# module_vs1003.net
KiCad netlist of a schematic drawn in EAGLE
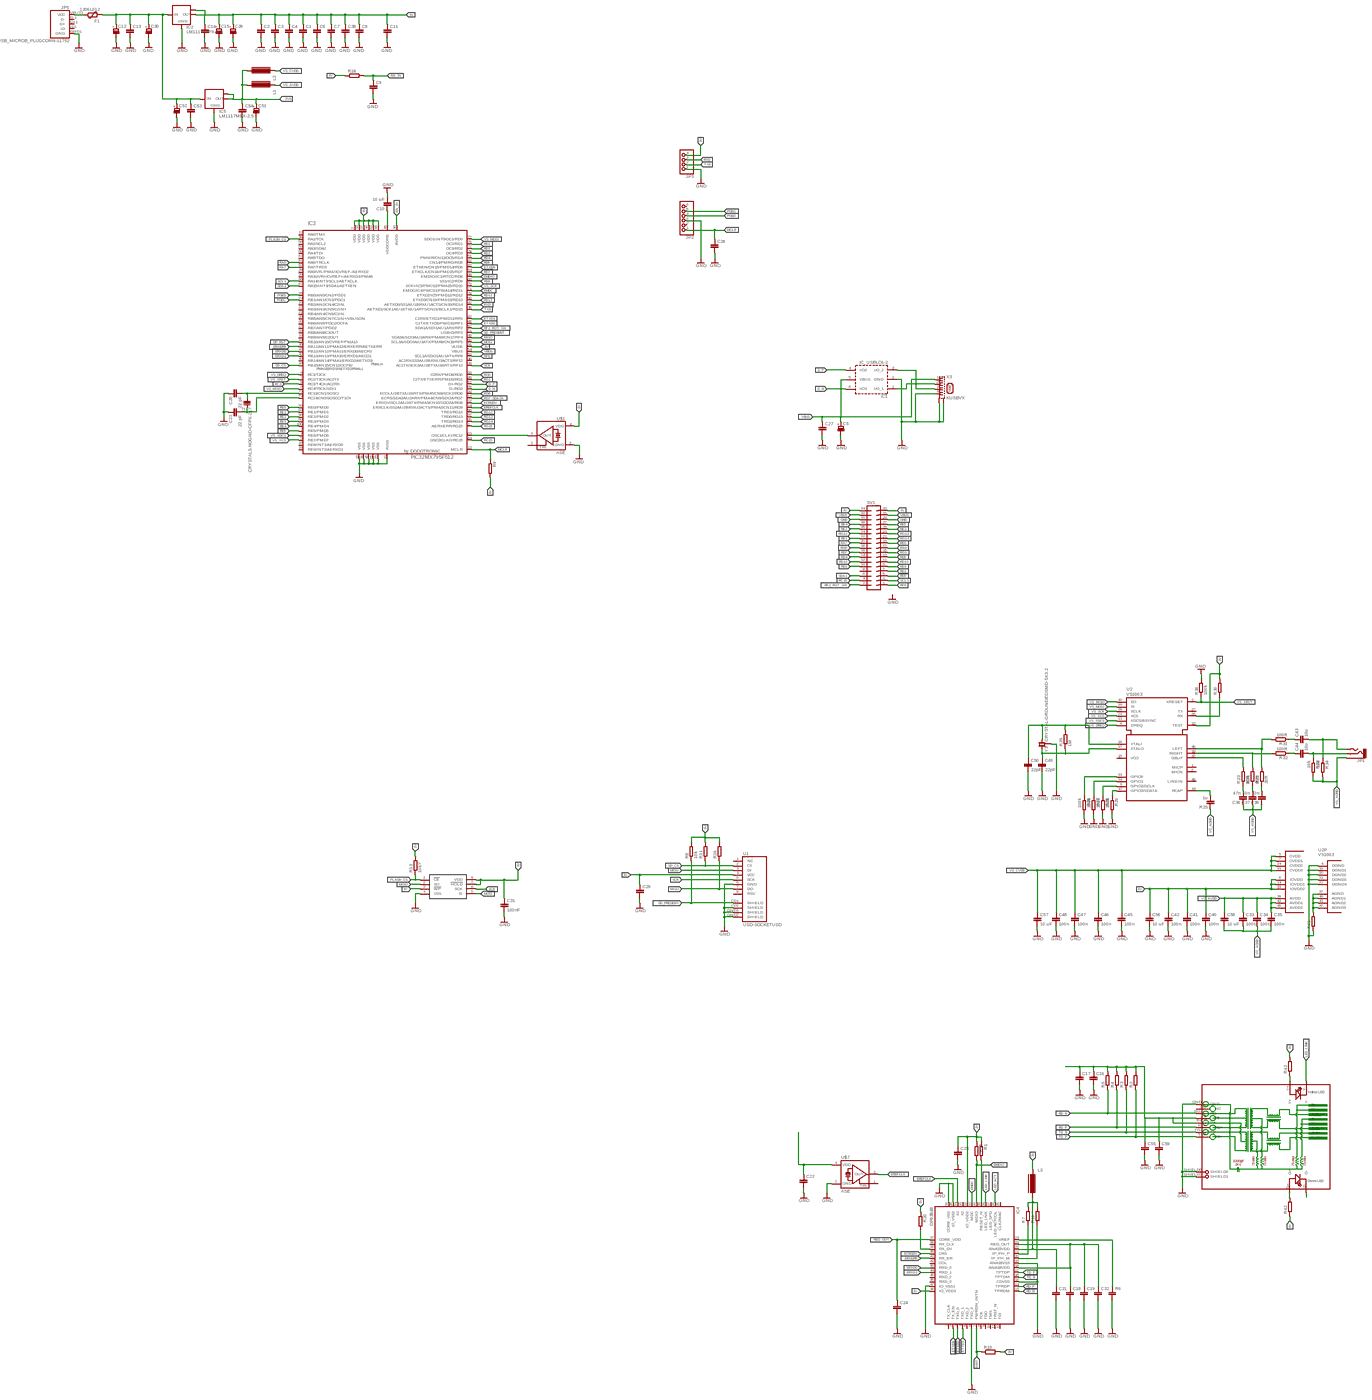
[diagram p0: schematic, sheet 1, overview]
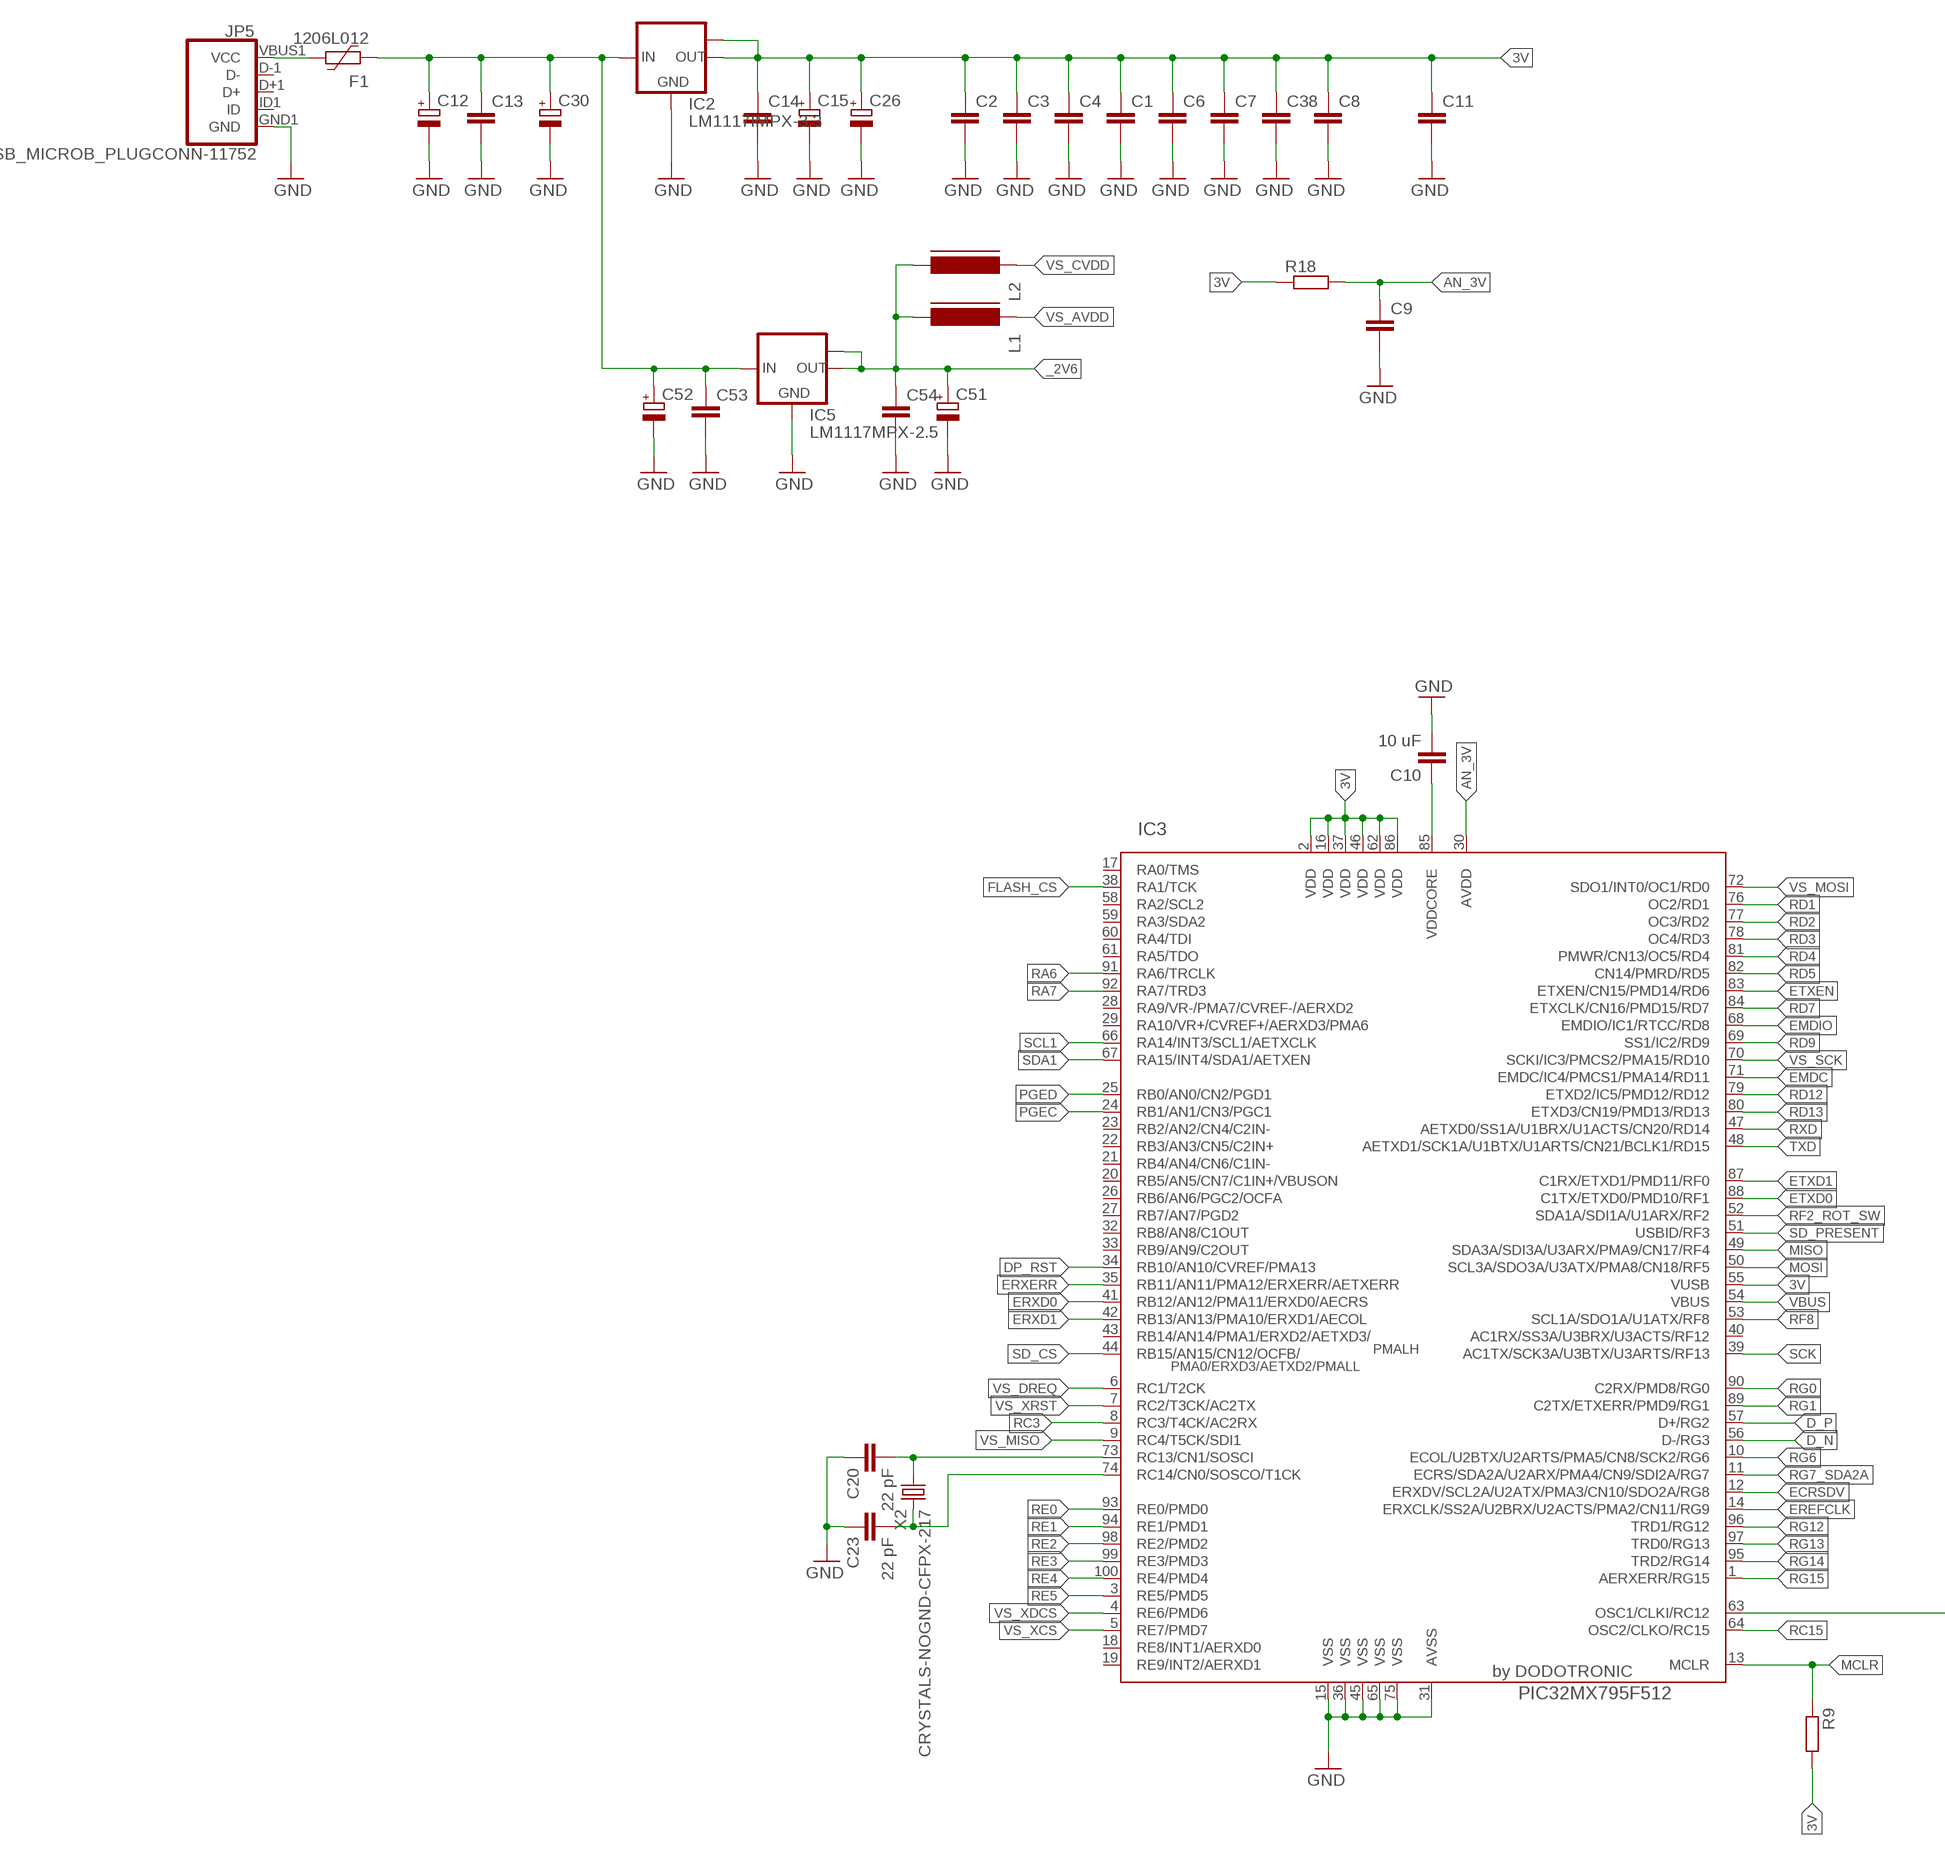
[diagram p1: schematic, sheet 1, part 1 of 4]
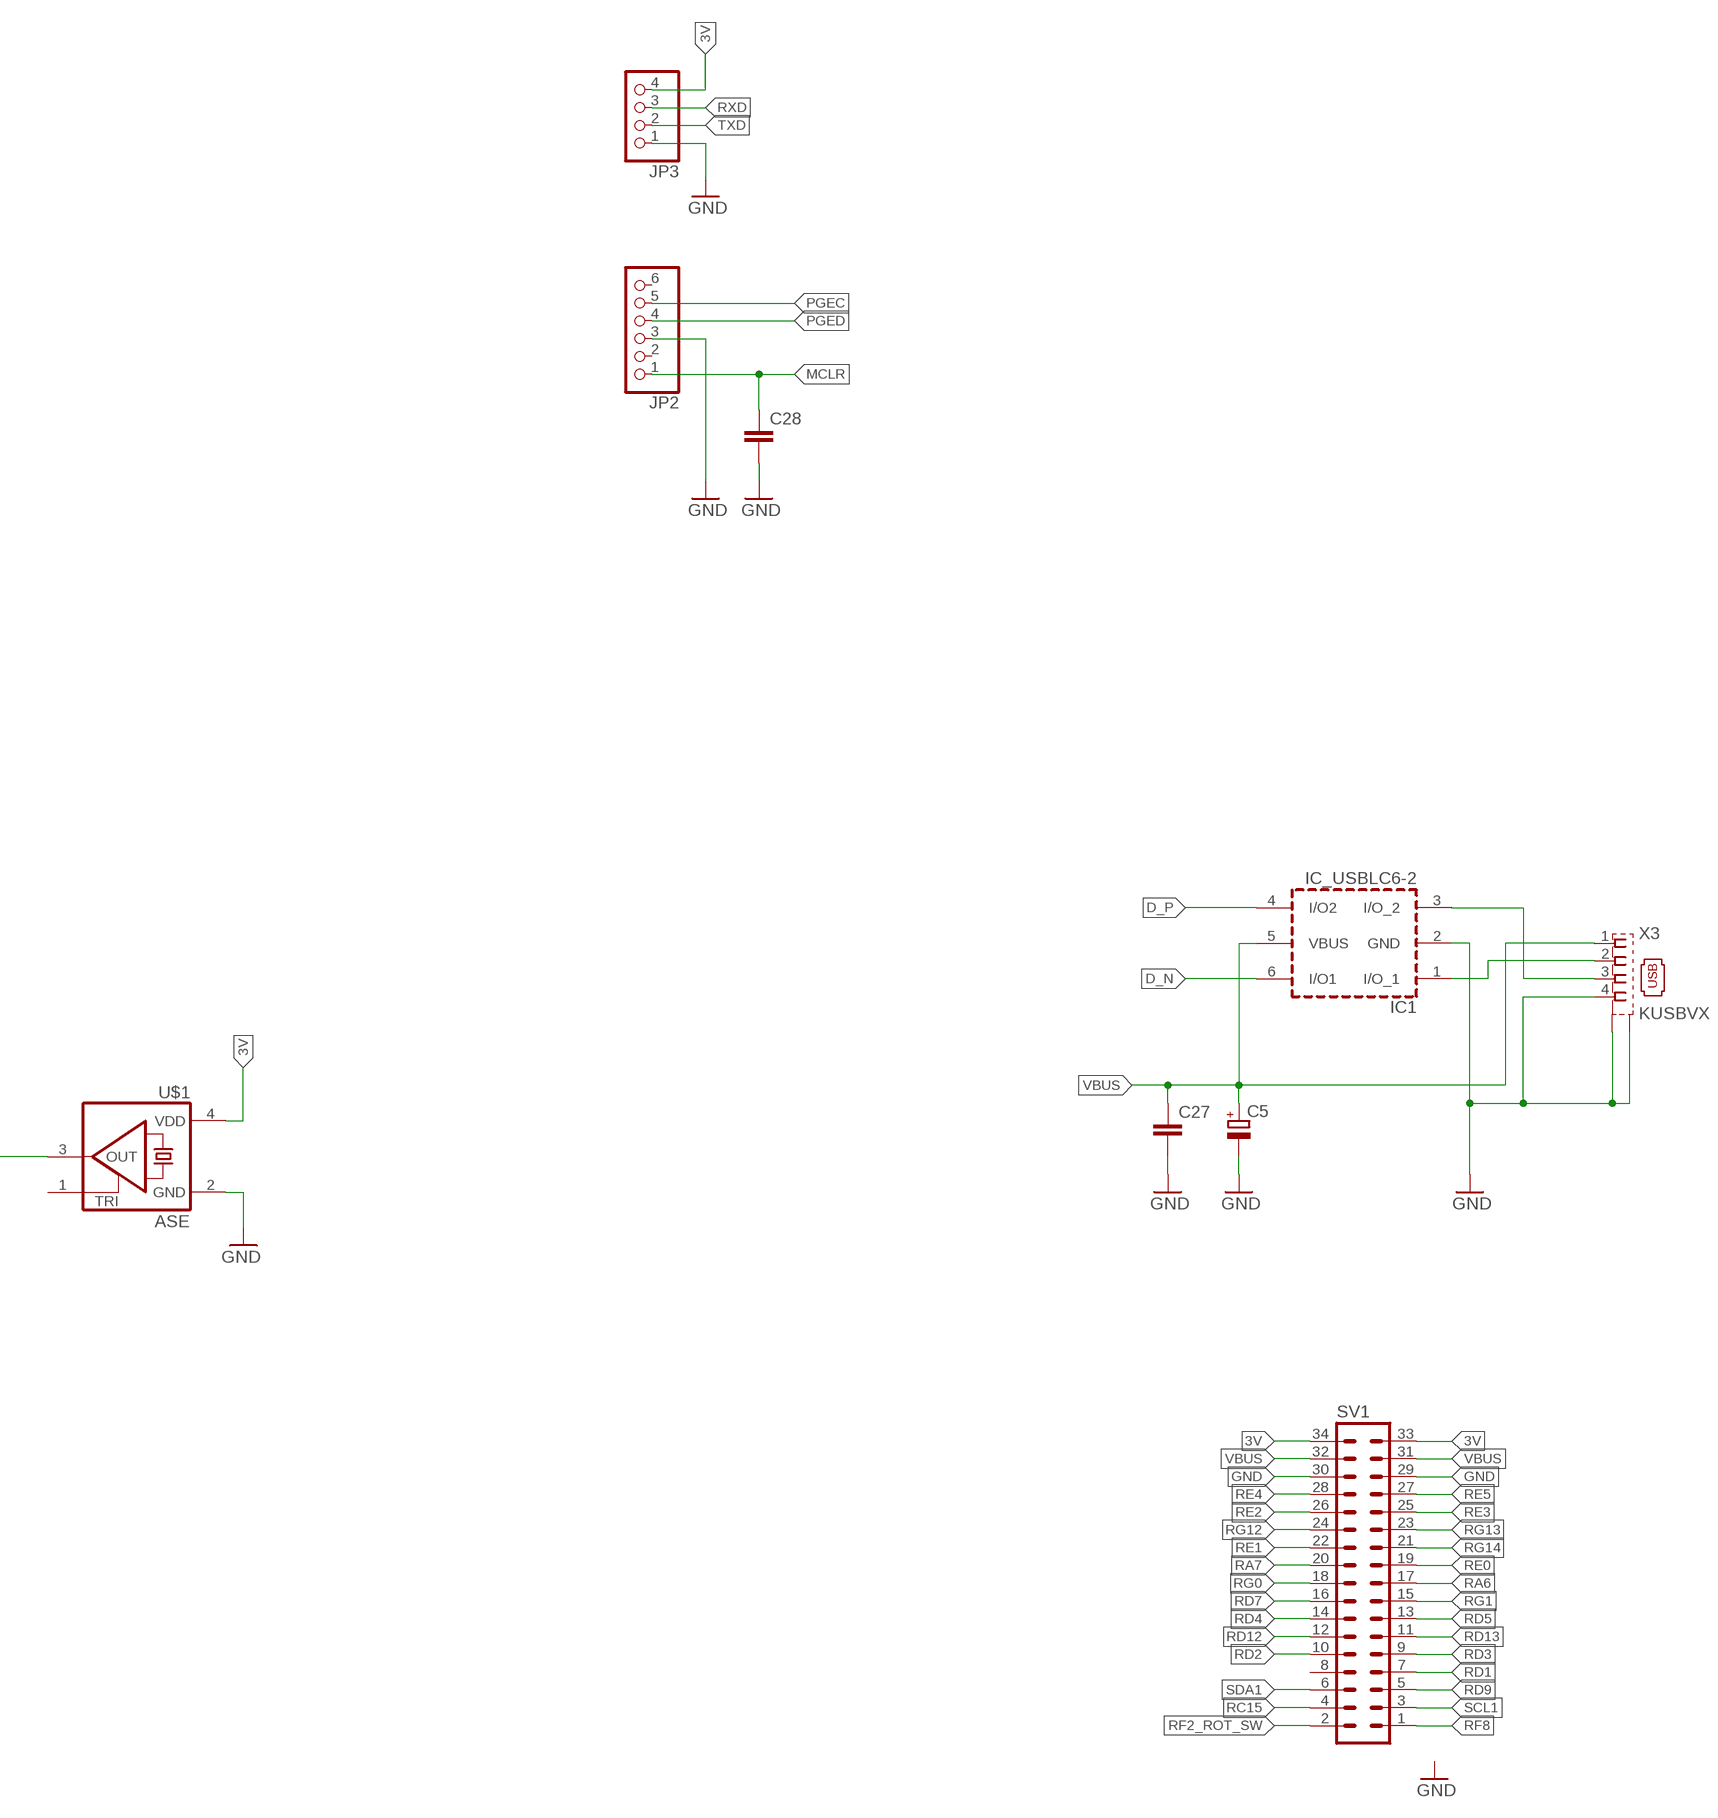
[diagram p2: schematic, sheet 1, part 2 of 4]
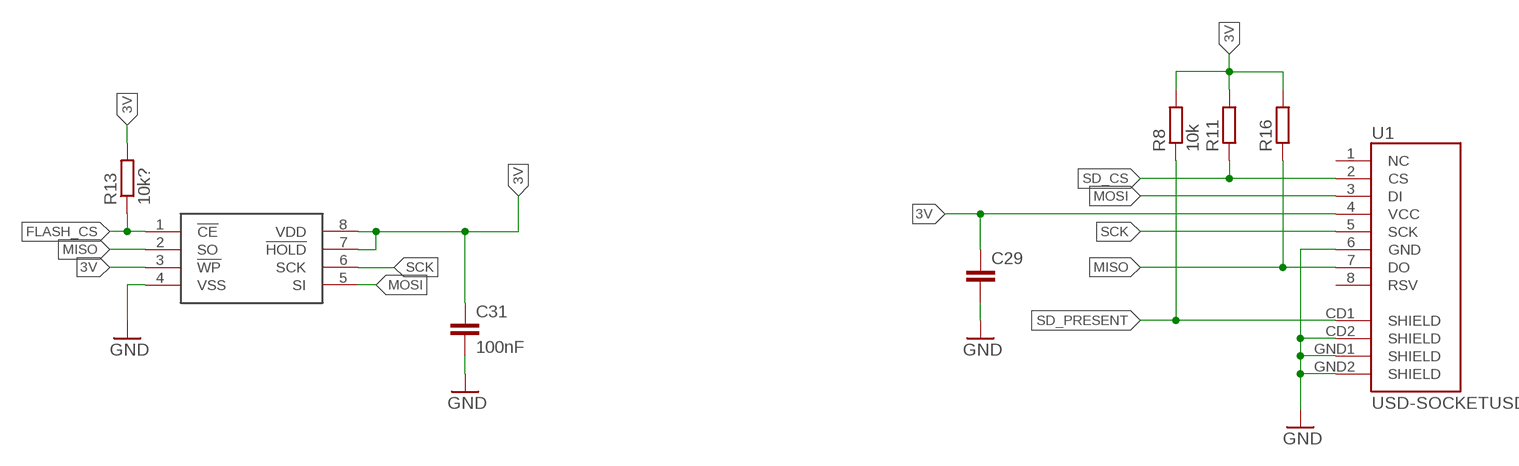
[diagram p3: schematic, sheet 1, part 3 of 4]
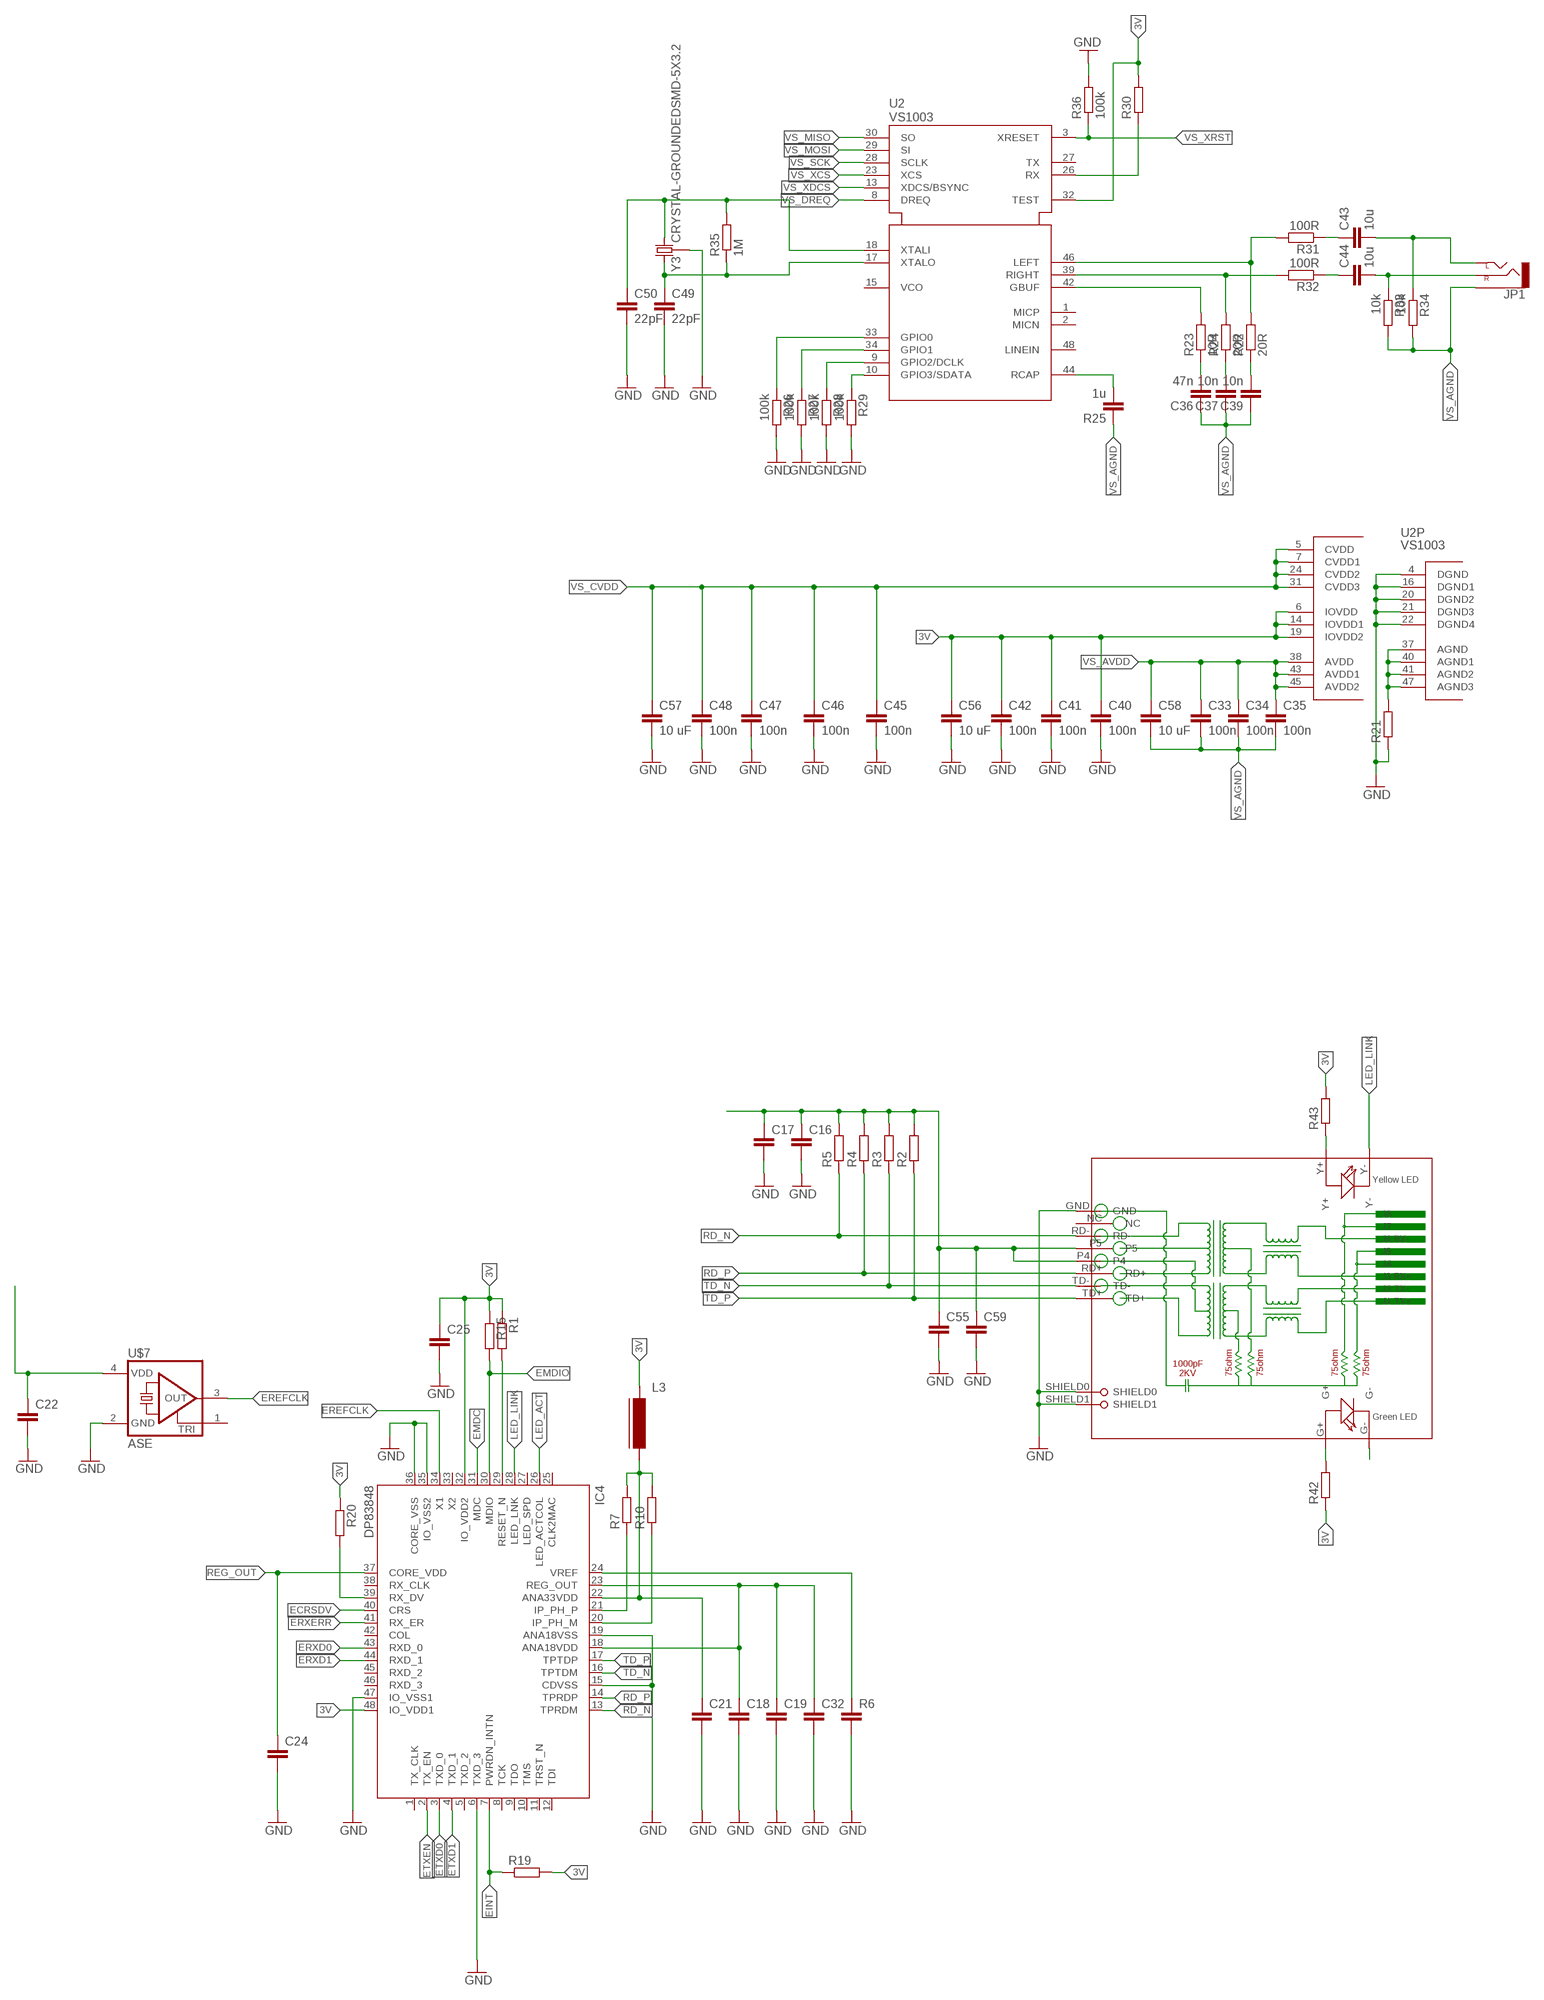
[diagram p4: schematic, sheet 1, part 4 of 4]

(export (version "E")
  (design (tool "Eeschema 10.0.6"))
  (components
    (comp (ref "C1")
      (value "C-EUC0402")
      (footprint "eagle-import:C0402")
      (libsource (lib "eagle-import") (part "C-EUC0402"))
    )
    (comp (ref "C2")
      (value "C-EUC0402")
      (footprint "eagle-import:C0402")
      (libsource (lib "eagle-import") (part "C-EUC0402"))
    )
    (comp (ref "C3")
      (value "C-EUC0402")
      (footprint "eagle-import:C0402")
      (libsource (lib "eagle-import") (part "C-EUC0402"))
    )
    (comp (ref "C4")
      (value "C-EUC0402")
      (footprint "eagle-import:C0402")
      (libsource (lib "eagle-import") (part "C-EUC0402"))
    )
    (comp (ref "C5")
      (value "CPOL-EUSMCA")
      (footprint "eagle-import:SMC_A")
      (libsource (lib "eagle-import") (part "CPOL-EUSMCA"))
    )
    (comp (ref "C6")
      (value "C-EUC0402")
      (footprint "eagle-import:C0402")
      (libsource (lib "eagle-import") (part "C-EUC0402"))
    )
    (comp (ref "C7")
      (value "C-EUC0402")
      (footprint "eagle-import:C0402")
      (libsource (lib "eagle-import") (part "C-EUC0402"))
    )
    (comp (ref "C8")
      (value "C-EUC0402")
      (footprint "eagle-import:C0402")
      (libsource (lib "eagle-import") (part "C-EUC0402"))
    )
    (comp (ref "C9")
      (value "C-EUC0402")
      (footprint "eagle-import:C0402")
      (libsource (lib "eagle-import") (part "C-EUC0402"))
    )
    (comp (ref "C10")
      (value "10 uF")
      (footprint "eagle-import:C0603")
      (libsource (lib "eagle-import") (part "C-EUC0603"))
    )
    (comp (ref "C11")
      (value "C-EUC0402")
      (footprint "eagle-import:C0402")
      (libsource (lib "eagle-import") (part "C-EUC0402"))
    )
    (comp (ref "C12")
      (value "CPOL-EUSMCB")
      (footprint "eagle-import:SMC_B")
      (libsource (lib "eagle-import") (part "CPOL-EUSMCB"))
    )
    (comp (ref "C13")
      (value "C-EUC0603")
      (footprint "eagle-import:C0603")
      (libsource (lib "eagle-import") (part "C-EUC0603"))
    )
    (comp (ref "C14")
      (value "C-EUC0603")
      (footprint "eagle-import:C0603")
      (libsource (lib "eagle-import") (part "C-EUC0603"))
    )
    (comp (ref "C15")
      (value "CPOL-EUSMCB")
      (footprint "eagle-import:SMC_B")
      (libsource (lib "eagle-import") (part "CPOL-EUSMCB"))
    )
    (comp (ref "C16")
      (value "C-EUC0603")
      (footprint "eagle-import:C0603")
      (libsource (lib "eagle-import") (part "C-EUC0603"))
    )
    (comp (ref "C17")
      (value "C-EUC0603")
      (footprint "eagle-import:C0603")
      (libsource (lib "eagle-import") (part "C-EUC0603"))
    )
    (comp (ref "C18")
      (value "C-EUC0402")
      (footprint "eagle-import:C0402")
      (libsource (lib "eagle-import") (part "C-EUC0402"))
    )
    (comp (ref "C19")
      (value "C-EUC0402")
      (footprint "eagle-import:C0402")
      (libsource (lib "eagle-import") (part "C-EUC0402"))
    )
    (comp (ref "C20")
      (value "22 pF")
      (footprint "eagle-import:C0603")
      (libsource (lib "eagle-import") (part "C-EUC0603"))
    )
    (comp (ref "C21")
      (value "C-EUC0402")
      (footprint "eagle-import:C0402")
      (libsource (lib "eagle-import") (part "C-EUC0402"))
    )
    (comp (ref "C22")
      (value "C-EUC0402")
      (footprint "eagle-import:C0402")
      (libsource (lib "eagle-import") (part "C-EUC0402"))
    )
    (comp (ref "C23")
      (value "22 pF")
      (footprint "eagle-import:C0603")
      (libsource (lib "eagle-import") (part "C-EUC0603"))
    )
    (comp (ref "C24")
      (value "C-EUC0603")
      (footprint "eagle-import:C0603")
      (libsource (lib "eagle-import") (part "C-EUC0603"))
    )
    (comp (ref "C25")
      (value "C-EUC0603")
      (footprint "eagle-import:C0603")
      (libsource (lib "eagle-import") (part "C-EUC0603"))
    )
    (comp (ref "C26")
      (value "CPOL-EUSMCA")
      (footprint "eagle-import:SMC_A")
      (libsource (lib "eagle-import") (part "CPOL-EUSMCA"))
    )
    (comp (ref "C27")
      (value "C-EUC0603")
      (footprint "eagle-import:C0603")
      (libsource (lib "eagle-import") (part "C-EUC0603"))
    )
    (comp (ref "C28")
      (value "C-EUC0603")
      (footprint "eagle-import:C0603")
      (libsource (lib "eagle-import") (part "C-EUC0603"))
    )
    (comp (ref "C29")
      (value "C-EUC0603")
      (footprint "eagle-import:C0603")
      (libsource (lib "eagle-import") (part "C-EUC0603"))
    )
    (comp (ref "C30")
      (value "CPOL-EUSMCA")
      (footprint "eagle-import:SMC_A")
      (libsource (lib "eagle-import") (part "CPOL-EUSMCA"))
    )
    (comp (ref "C31")
      (value "100nF")
      (footprint "eagle-import:C0603")
      (libsource (lib "eagle-import") (part "C-EUC0603"))
    )
    (comp (ref "C32")
      (value "C-EUC0603")
      (footprint "eagle-import:C0603")
      (libsource (lib "eagle-import") (part "C-EUC0603"))
    )
    (comp (ref "C33")
      (value "100n")
      (footprint "eagle-import:C0603")
      (libsource (lib "eagle-import") (part "C-EUC0603"))
    )
    (comp (ref "C34")
      (value "100n")
      (footprint "eagle-import:C0603")
      (libsource (lib "eagle-import") (part "C-EUC0603"))
    )
    (comp (ref "C35")
      (value "100n")
      (footprint "eagle-import:C0603")
      (libsource (lib "eagle-import") (part "C-EUC0603"))
    )
    (comp (ref "C36")
      (value "47n")
      (footprint "eagle-import:C0603")
      (libsource (lib "eagle-import") (part "C-EUC0603"))
    )
    (comp (ref "C37")
      (value "10n")
      (footprint "eagle-import:C0603")
      (libsource (lib "eagle-import") (part "C-EUC0603"))
    )
    (comp (ref "C38")
      (value "C-EUC0402")
      (footprint "eagle-import:C0402")
      (libsource (lib "eagle-import") (part "C-EUC0402"))
    )
    (comp (ref "C39")
      (value "10n")
      (footprint "eagle-import:C0603")
      (libsource (lib "eagle-import") (part "C-EUC0603"))
    )
    (comp (ref "C40")
      (value "100n")
      (footprint "eagle-import:C0402")
      (libsource (lib "eagle-import") (part "C-EUC0402"))
    )
    (comp (ref "C41")
      (value "100n")
      (footprint "eagle-import:C0402")
      (libsource (lib "eagle-import") (part "C-EUC0402"))
    )
    (comp (ref "C42")
      (value "100n")
      (footprint "eagle-import:C0402")
      (libsource (lib "eagle-import") (part "C-EUC0402"))
    )
    (comp (ref "C43")
      (value "10u")
      (footprint "eagle-import:C0603")
      (libsource (lib "eagle-import") (part "C-EUC0603"))
    )
    (comp (ref "C44")
      (value "10u")
      (footprint "eagle-import:C0603")
      (libsource (lib "eagle-import") (part "C-EUC0603"))
    )
    (comp (ref "C45")
      (value "100n")
      (footprint "eagle-import:C0402")
      (libsource (lib "eagle-import") (part "C-EUC0402"))
    )
    (comp (ref "C46")
      (value "100n")
      (footprint "eagle-import:C0603")
      (libsource (lib "eagle-import") (part "C-EUC0603"))
    )
    (comp (ref "C47")
      (value "100n")
      (footprint "eagle-import:C0603")
      (libsource (lib "eagle-import") (part "C-EUC0603"))
    )
    (comp (ref "C48")
      (value "100n")
      (footprint "eagle-import:C0603")
      (libsource (lib "eagle-import") (part "C-EUC0603"))
    )
    (comp (ref "C49")
      (value "22pF")
      (footprint "eagle-import:C0603")
      (libsource (lib "eagle-import") (part "C-EUC0603"))
    )
    (comp (ref "C50")
      (value "22pF")
      (footprint "eagle-import:C0603")
      (libsource (lib "eagle-import") (part "C-EUC0603"))
    )
    (comp (ref "C51")
      (value "CPOL-EUSMCB")
      (footprint "eagle-import:SMC_B")
      (libsource (lib "eagle-import") (part "CPOL-EUSMCB"))
    )
    (comp (ref "C52")
      (value "CPOL-EUSMCB")
      (footprint "eagle-import:SMC_B")
      (libsource (lib "eagle-import") (part "CPOL-EUSMCB"))
    )
    (comp (ref "C53")
      (value "C-EUC1206")
      (footprint "eagle-import:C1206")
      (libsource (lib "eagle-import") (part "C-EUC1206"))
    )
    (comp (ref "C54")
      (value "C-EUC1206")
      (footprint "eagle-import:C1206")
      (libsource (lib "eagle-import") (part "C-EUC1206"))
    )
    (comp (ref "C55")
      (value "C-EUC0603")
      (footprint "eagle-import:C0603")
      (libsource (lib "eagle-import") (part "C-EUC0603"))
    )
    (comp (ref "C56")
      (value "10 uF")
      (footprint "eagle-import:C0603")
      (libsource (lib "eagle-import") (part "C-EUC0603"))
    )
    (comp (ref "C57")
      (value "10 uF")
      (footprint "eagle-import:C0603")
      (libsource (lib "eagle-import") (part "C-EUC0603"))
    )
    (comp (ref "C58")
      (value "10 uF")
      (footprint "eagle-import:C0603")
      (libsource (lib "eagle-import") (part "C-EUC0603"))
    )
    (comp (ref "C59")
      (value "C-EUC0603")
      (footprint "eagle-import:C0603")
      (libsource (lib "eagle-import") (part "C-EUC0603"))
    )
    (comp (ref "F1")
      (value "1206L012")
      (footprint "eagle-import:1206L")
      (fields (field (name "MF") "Littelfuse"))
      (libsource (lib "eagle-import") (part "?1206L012"))
    )
    (comp (ref "IC1")
      (value "IC_USBLC6-2")
      (footprint "eagle-import:SOT-23-6L")
      (libsource (lib "eagle-import") (part "IC_USBLC6-2"))
    )
    (comp (ref "IC2")
      (value "LM1117IMPX-3.3")
      (footprint "eagle-import:SOT223")
      (libsource (lib "eagle-import") (part "LM1117IMPX-3.3"))
    )
    (comp (ref "IC3")
      (value "PIC32MX795F512")
      (footprint "eagle-import:TQFP100_12X12")
      (libsource (lib "eagle-import") (part "PIC32MX795F512"))
    )
    (comp (ref "IC4")
      (value "DP83848")
      (footprint "eagle-import:LQFP48")
      (fields (field (name "MPN") "DP83848VYB"))
      (libsource (lib "eagle-import") (part "DP83848"))
    )
    (comp (ref "IC5")
      (value "LM1117MPX-2.5")
      (footprint "eagle-import:SOT223")
      (libsource (lib "eagle-import") (part "LM1117MPX-2.5"))
    )
    (comp (ref "JP1")
      (value "AUDIO-JACKAUDIO_JACK2")
      (footprint "eagle-import:AUDIO-JACK2")
      (libsource (lib "eagle-import") (part "AUDIO-JACKAUDIO_JACK2"))
    )
    (comp (ref "JP2")
      (value "PINHD-1X6")
      (footprint "eagle-import:1X06")
      (libsource (lib "eagle-import") (part "PINHD-1X6"))
    )
    (comp (ref "JP3")
      (value "PINHD-1X4")
      (footprint "eagle-import:1X04")
      (libsource (lib "eagle-import") (part "PINHD-1X4"))
    )
    (comp (ref "JP5")
      (value "USB_MICROB_PLUGCONN-11752")
      (footprint "eagle-import:USB-B-MICRO-SMD_V03")
      (libsource (lib "eagle-import") (part "USB_MICROB_PLUGCONN-11752"))
    )
    (comp (ref "L1")
      (value "FERRITE-0805")
      (footprint "eagle-import:FB805")
      (libsource (lib "eagle-import") (part "FERRITE-0805"))
    )
    (comp (ref "L2")
      (value "FERRITE-0805")
      (footprint "eagle-import:FB805")
      (libsource (lib "eagle-import") (part "FERRITE-0805"))
    )
    (comp (ref "L3")
      (value "FERRITE-0805")
      (footprint "eagle-import:FB805")
      (libsource (lib "eagle-import") (part "FERRITE-0805"))
    )
    (comp (ref "R1")
      (value "R-EU_R0402")
      (footprint "eagle-import:R0402")
      (libsource (lib "eagle-import") (part "R-EU_R0402"))
    )
    (comp (ref "R2")
      (value "R-EU_R0603")
      (footprint "eagle-import:R0603")
      (libsource (lib "eagle-import") (part "R-EU_R0603"))
    )
    (comp (ref "R3")
      (value "R-EU_R0603")
      (footprint "eagle-import:R0603")
      (libsource (lib "eagle-import") (part "R-EU_R0603"))
    )
    (comp (ref "R4")
      (value "R-EU_R0603")
      (footprint "eagle-import:R0603")
      (libsource (lib "eagle-import") (part "R-EU_R0603"))
    )
    (comp (ref "R5")
      (value "R-EU_R0603")
      (footprint "eagle-import:R0603")
      (libsource (lib "eagle-import") (part "R-EU_R0603"))
    )
    (comp (ref "R6")
      (value "C-EUC0603")
      (footprint "eagle-import:C0603")
      (libsource (lib "eagle-import") (part "C-EUC0603"))
    )
    (comp (ref "R7")
      (value "R-EU_R0402")
      (footprint "eagle-import:R0402")
      (libsource (lib "eagle-import") (part "R-EU_R0402"))
    )
    (comp (ref "R8")
      (value "10k")
      (footprint "eagle-import:R0603")
      (libsource (lib "eagle-import") (part "R-EU_R0603"))
    )
    (comp (ref "R9")
      (value "R-EU_R0603")
      (footprint "eagle-import:R0603")
      (libsource (lib "eagle-import") (part "R-EU_R0603"))
    )
    (comp (ref "R10")
      (value "R-EU_R0402")
      (footprint "eagle-import:R0402")
      (libsource (lib "eagle-import") (part "R-EU_R0402"))
    )
    (comp (ref "R11")
      (value "R-EU_R0603")
      (footprint "eagle-import:R0603")
      (libsource (lib "eagle-import") (part "R-EU_R0603"))
    )
    (comp (ref "R13")
      (value "10k?")
      (footprint "eagle-import:R0603")
      (libsource (lib "eagle-import") (part "R-EU_R0603"))
    )
    (comp (ref "R15")
      (value "R-EU_R0603")
      (footprint "eagle-import:R0603")
      (libsource (lib "eagle-import") (part "R-EU_R0603"))
    )
    (comp (ref "R16")
      (value "R-EU_R0603")
      (footprint "eagle-import:R0603")
      (libsource (lib "eagle-import") (part "R-EU_R0603"))
    )
    (comp (ref "R18")
      (value "R-EU_R0805")
      (footprint "eagle-import:R0805")
      (libsource (lib "eagle-import") (part "R-EU_R0805"))
    )
    (comp (ref "R19")
      (value "R-EU_R0402")
      (footprint "eagle-import:R0402")
      (libsource (lib "eagle-import") (part "R-EU_R0402"))
    )
    (comp (ref "R20")
      (value "R-EU_R0603")
      (footprint "eagle-import:R0603")
      (libsource (lib "eagle-import") (part "R-EU_R0603"))
    )
    (comp (ref "R21")
      (value "R-EU_R0603")
      (footprint "eagle-import:R0603")
      (libsource (lib "eagle-import") (part "R-EU_R0603"))
    )
    (comp (ref "R22")
      (value "20R")
      (footprint "eagle-import:R0603")
      (libsource (lib "eagle-import") (part "R-EU_R0603"))
    )
    (comp (ref "R23")
      (value "10R")
      (footprint "eagle-import:R0603")
      (libsource (lib "eagle-import") (part "R-EU_R0603"))
    )
    (comp (ref "R24")
      (value "20R")
      (footprint "eagle-import:R0603")
      (libsource (lib "eagle-import") (part "R-EU_R0603"))
    )
    (comp (ref "R25")
      (value "1u")
      (footprint "eagle-import:C0603")
      (libsource (lib "eagle-import") (part "C-EUC0603"))
    )
    (comp (ref "R26")
      (value "100k")
      (footprint "eagle-import:R0402")
      (libsource (lib "eagle-import") (part "R-EU_R0402"))
    )
    (comp (ref "R27")
      (value "100k")
      (footprint "eagle-import:R0402")
      (libsource (lib "eagle-import") (part "R-EU_R0402"))
    )
    (comp (ref "R28")
      (value "100k")
      (footprint "eagle-import:R0402")
      (libsource (lib "eagle-import") (part "R-EU_R0402"))
    )
    (comp (ref "R29")
      (value "100k")
      (footprint "eagle-import:R0402")
      (libsource (lib "eagle-import") (part "R-EU_R0402"))
    )
    (comp (ref "R30")
      (value "R-EU_0204/7")
      (footprint "eagle-import:0204_7")
      (libsource (lib "eagle-import") (part "R-EU_0204/7"))
    )
    (comp (ref "R31")
      (value "100R")
      (footprint "eagle-import:R0603")
      (libsource (lib "eagle-import") (part "R-EU_R0603"))
    )
    (comp (ref "R32")
      (value "100R")
      (footprint "eagle-import:R0603")
      (libsource (lib "eagle-import") (part "R-EU_R0603"))
    )
    (comp (ref "R33")
      (value "10k")
      (footprint "eagle-import:R0603")
      (libsource (lib "eagle-import") (part "R-EU_R0603"))
    )
    (comp (ref "R34")
      (value "10k")
      (footprint "eagle-import:R0603")
      (libsource (lib "eagle-import") (part "R-EU_R0603"))
    )
    (comp (ref "R35")
      (value "1M")
      (footprint "eagle-import:R0603")
      (libsource (lib "eagle-import") (part "R-EU_R0603"))
    )
    (comp (ref "R36")
      (value "100k")
      (footprint "eagle-import:R0603")
      (libsource (lib "eagle-import") (part "R-EU_R0603"))
    )
    (comp (ref "R42")
      (value "R-EU_R0603")
      (footprint "eagle-import:R0603")
      (libsource (lib "eagle-import") (part "R-EU_R0603"))
    )
    (comp (ref "R43")
      (value "R-EU_R0603")
      (footprint "eagle-import:R0603")
      (libsource (lib "eagle-import") (part "R-EU_R0603"))
    )
    (comp (ref "RJ1")
      (value "HR911105A")
      (footprint "eagle-import:HR911105A")
      (libsource (lib "eagle-import") (part "HR911105A"))
    )
    (comp (ref "SV1")
      (value "ML34L")
      (footprint "eagle-import:ML34L")
      (libsource (lib "eagle-import") (part "ML34L"))
    )
    (comp (ref "U$1")
      (value "ASE")
      (footprint "eagle-import:ASE")
      (libsource (lib "eagle-import") (part "ASE"))
    )
    (comp (ref "U$2")
      (value "SST25VF016BSO8M")
      (footprint "eagle-import:SO-08M")
      (libsource (lib "eagle-import") (part "SST25VF016BSO8M"))
    )
    (comp (ref "U$7")
      (value "ASE")
      (footprint "eagle-import:ASE")
      (libsource (lib "eagle-import") (part "ASE"))
    )
    (comp (ref "U1")
      (value "USD-SOCKETUSD")
      (footprint "eagle-import:USD-SOCKET-PP")
      (libsource (lib "eagle-import") (part "USD-SOCKETUSD"))
    )
    (comp (ref "U2")
      (value "VS1003")
      (footprint "eagle-import:LQFP48")
      (libsource (lib "eagle-import") (part "VS1003"))
    )
    (comp (ref "X2")
      (value "CRYSTALS-NOGND-CFPX-217")
      (footprint "eagle-import:3.2X1.5-2-PAD")
      (libsource (lib "eagle-import") (part "CRYSTALS-NOGND-CFPX-217"))
    )
    (comp (ref "X3")
      (value "KUSBVX")
      (footprint "eagle-import:KUSBVX")
      (libsource (lib "eagle-import") (part "KUSBVX"))
    )
    (comp (ref "Y3")
      (value "CRYSTAL-GROUNDEDSMD-5X3.2")
      (footprint "eagle-import:CRYSTAL-SMD-5X3.2-4PAD")
      (libsource (lib "eagle-import") (part "CRYSTAL-GROUNDEDSMD-5X3.2"))
    )
  )
  (nets
    (net (code "1") (name "/A3V") (class "Default")
      (node (ref "C16") (pin "1") (pinfunction "1_1") (pintype "passive"))
      (node (ref "C17") (pin "1") (pinfunction "1_1") (pintype "passive"))
      (node (ref "C21") (pin "1") (pinfunction "1_1") (pintype "passive"))
      (node (ref "C55") (pin "1") (pinfunction "1_1") (pintype "passive"))
      (node (ref "C59") (pin "1") (pinfunction "1_1") (pintype "passive"))
      (node (ref "IC4") (pin "22") (pinfunction "ANA33VDD_22") (pintype "power_in"))
      (node (ref "L3") (pin "2") (pinfunction "2_2") (pintype "passive"))
      (node (ref "R10") (pin "2") (pinfunction "2_2") (pintype "passive"))
      (node (ref "R2") (pin "2") (pinfunction "2_2") (pintype "passive"))
      (node (ref "R3") (pin "2") (pinfunction "2_2") (pintype "passive"))
      (node (ref "R4") (pin "2") (pinfunction "2_2") (pintype "passive"))
      (node (ref "R5") (pin "2") (pinfunction "2_2") (pintype "passive"))
      (node (ref "R7") (pin "2") (pinfunction "2_2") (pintype "passive"))
      (node (ref "RJ1") (pin "P4") (pinfunction "P4_P4") (pintype "bidirectional"))
      (node (ref "RJ1") (pin "P5") (pinfunction "P5_P5") (pintype "bidirectional"))
    )
    (net (code "2") (name "3V") (class "Default")
      (node (ref "C1") (pin "1") (pinfunction "1_1") (pintype "passive"))
      (node (ref "C11") (pin "1") (pinfunction "1_1") (pintype "passive"))
      (node (ref "C14") (pin "1") (pinfunction "1_1") (pintype "passive"))
      (node (ref "C15") (pin "+") (pinfunction "+_+") (pintype "passive"))
      (node (ref "C2") (pin "1") (pinfunction "1_1") (pintype "passive"))
      (node (ref "C22") (pin "1") (pinfunction "1_1") (pintype "passive"))
      (node (ref "C25") (pin "1") (pinfunction "1_1") (pintype "passive"))
      (node (ref "C26") (pin "+") (pinfunction "+_+") (pintype "passive"))
      (node (ref "C29") (pin "1") (pinfunction "1_1") (pintype "passive"))
      (node (ref "C3") (pin "1") (pinfunction "1_1") (pintype "passive"))
      (node (ref "C31") (pin "1") (pinfunction "1_1") (pintype "passive"))
      (node (ref "C38") (pin "1") (pinfunction "1_1") (pintype "passive"))
      (node (ref "C4") (pin "1") (pinfunction "1_1") (pintype "passive"))
      (node (ref "C40") (pin "1") (pinfunction "1_1") (pintype "passive"))
      (node (ref "C41") (pin "1") (pinfunction "1_1") (pintype "passive"))
      (node (ref "C42") (pin "1") (pinfunction "1_1") (pintype "passive"))
      (node (ref "C56") (pin "1") (pinfunction "1_1") (pintype "passive"))
      (node (ref "C6") (pin "1") (pinfunction "1_1") (pintype "passive"))
      (node (ref "C7") (pin "1") (pinfunction "1_1") (pintype "passive"))
      (node (ref "C8") (pin "1") (pinfunction "1_1") (pintype "passive"))
      (node (ref "IC2") (pin "2") (pinfunction "OUT_2") (pintype "passive"))
      (node (ref "IC2") (pin "TAB") (pinfunction "OUT1_TAB") (pintype "passive"))
      (node (ref "IC3") (pin "16") (pinfunction "VDD_16") (pintype "power_in"))
      (node (ref "IC3") (pin "2") (pinfunction "VDD_2") (pintype "power_in"))
      (node (ref "IC3") (pin "37") (pinfunction "VDD_37") (pintype "power_in"))
      (node (ref "IC3") (pin "46") (pinfunction "VDD_46") (pintype "power_in"))
      (node (ref "IC3") (pin "55") (pinfunction "VUSB_55") (pintype "bidirectional"))
      (node (ref "IC3") (pin "62") (pinfunction "VDD_62") (pintype "power_in"))
      (node (ref "IC3") (pin "86") (pinfunction "VDD_86") (pintype "power_in"))
      (node (ref "IC4") (pin "32") (pinfunction "IO_VDD2_32") (pintype "power_in"))
      (node (ref "IC4") (pin "48") (pinfunction "IO_VDD1_48") (pintype "power_in"))
      (node (ref "JP3") (pin "4") (pinfunction "4_4") (pintype "passive"))
      (node (ref "L3") (pin "1") (pinfunction "1_1") (pintype "passive"))
      (node (ref "R1") (pin "1") (pinfunction "1_1") (pintype "passive"))
      (node (ref "R11") (pin "2") (pinfunction "2_2") (pintype "passive"))
      (node (ref "R13") (pin "2") (pinfunction "2_2") (pintype "passive"))
      (node (ref "R15") (pin "1") (pinfunction "1_1") (pintype "passive"))
      (node (ref "R16") (pin "2") (pinfunction "2_2") (pintype "passive"))
      (node (ref "R18") (pin "1") (pinfunction "1_1") (pintype "passive"))
      (node (ref "R19") (pin "2") (pinfunction "2_2") (pintype "passive"))
      (node (ref "R20") (pin "1") (pinfunction "1_1") (pintype "passive"))
      (node (ref "R30") (pin "2") (pinfunction "2_2") (pintype "passive"))
      (node (ref "R42") (pin "1") (pinfunction "1_1") (pintype "passive"))
      (node (ref "R43") (pin "2") (pinfunction "2_2") (pintype "passive"))
      (node (ref "R8") (pin "2") (pinfunction "2_2") (pintype "passive"))
      (node (ref "R9") (pin "2") (pinfunction "2_2") (pintype "passive"))
      (node (ref "SV1") (pin "33") (pinfunction "33_33") (pintype "passive"))
      (node (ref "SV1") (pin "34") (pinfunction "34_34") (pintype "passive"))
      (node (ref "U$1") (pin "4") (pinfunction "VDD_4") (pintype "power_in"))
      (node (ref "U$2") (pin "3") (pinfunction "~{WP}_3") (pintype "bidirectional"))
      (node (ref "U$2") (pin "7") (pinfunction "~{HOLD}_7") (pintype "bidirectional"))
      (node (ref "U$2") (pin "8") (pinfunction "VDD_8") (pintype "bidirectional"))
      (node (ref "U$7") (pin "4") (pinfunction "VDD_4") (pintype "power_in"))
      (node (ref "U1") (pin "4") (pinfunction "VCC_4") (pintype "bidirectional"))
      (node (ref "U2") (pin "14") (pinfunction "IOVDD1_14") (pintype "power_in"))
      (node (ref "U2") (pin "19") (pinfunction "IOVDD2_19") (pintype "power_in"))
      (node (ref "U2") (pin "32") (pinfunction "TEST_32") (pintype "bidirectional"))
      (node (ref "U2") (pin "6") (pinfunction "IOVDD_6") (pintype "power_in"))
    )
    (net (code "3") (name "AN_3V") (class "Default")
      (node (ref "C9") (pin "1") (pinfunction "1_1") (pintype "passive"))
      (node (ref "IC3") (pin "30") (pinfunction "AVDD_30") (pintype "bidirectional"))
      (node (ref "R18") (pin "2") (pinfunction "2_2") (pintype "passive"))
    )
    (net (code "4") (name "DP_RST") (class "Default")
      (node (ref "IC3") (pin "34") (pinfunction "RB10/AN10/CVREF/PMA13_34") (pintype "bidirectional"))
      (node (ref "IC4") (pin "29") (pinfunction "RESET_N_29") (pintype "input"))
      (node (ref "R1") (pin "2") (pinfunction "2_2") (pintype "passive"))
    )
    (net (code "5") (name "D_N") (class "Default")
      (node (ref "IC1") (pin "6") (pinfunction "I/O1_6") (pintype "bidirectional"))
      (node (ref "IC3") (pin "56") (pinfunction "D-/RG3_56") (pintype "bidirectional"))
    )
    (net (code "6") (name "D_P") (class "Default")
      (node (ref "IC1") (pin "4") (pinfunction "I/O2_4") (pintype "bidirectional"))
      (node (ref "IC3") (pin "57") (pinfunction "D+/RG2_57") (pintype "bidirectional"))
    )
    (net (code "7") (name "ECRSDV") (class "Default")
      (node (ref "IC3") (pin "12") (pinfunction "ERXDV/SCL2A/U2ATX/PMA3/CN10/SDO2A/RG8_12") (pintype "bidirectional"))
      (node (ref "IC4") (pin "40") (pinfunction "CRS_40") (pintype "bidirectional"))
    )
    (net (code "8") (name "EINT") (class "Default")
      (node (ref "IC4") (pin "7") (pinfunction "PWRDN_INTN_7") (pintype "bidirectional"))
      (node (ref "R19") (pin "1") (pinfunction "1_1") (pintype "passive"))
    )
    (net (code "9") (name "EMDC") (class "Default")
      (node (ref "IC3") (pin "71") (pinfunction "EMDC/IC4/PMCS1/PMA14/RD11_71") (pintype "bidirectional"))
      (node (ref "IC4") (pin "31") (pinfunction "MDC_31") (pintype "input"))
    )
    (net (code "10") (name "EMDIO") (class "Default")
      (node (ref "IC3") (pin "68") (pinfunction "EMDIO/IC1/RTCC/RD8_68") (pintype "bidirectional"))
      (node (ref "IC4") (pin "30") (pinfunction "MDIO_30") (pintype "bidirectional"))
      (node (ref "R15") (pin "2") (pinfunction "2_2") (pintype "passive"))
    )
    (net (code "11") (name "EREFCLK") (class "Default")
      (node (ref "IC3") (pin "14") (pinfunction "ERXCLK/SS2A/U2BRX/U2ACTS/PMA2/CN11/RG9_14") (pintype "bidirectional"))
      (node (ref "IC4") (pin "34") (pinfunction "X1_34") (pintype "input"))
      (node (ref "U$7") (pin "3") (pinfunction "OUT_3") (pintype "output"))
    )
    (net (code "12") (name "ERXD0") (class "Default")
      (node (ref "IC3") (pin "41") (pinfunction "RB12/AN12/PMA11/ERXD0/AECRS_41") (pintype "bidirectional"))
      (node (ref "IC4") (pin "43") (pinfunction "RXD_0_43") (pintype "bidirectional"))
    )
    (net (code "13") (name "ERXD1") (class "Default")
      (node (ref "IC3") (pin "42") (pinfunction "RB13/AN13/PMA10/ERXD1/AECOL_42") (pintype "bidirectional"))
      (node (ref "IC4") (pin "44") (pinfunction "RXD_1_44") (pintype "bidirectional"))
    )
    (net (code "14") (name "ERXERR") (class "Default")
      (node (ref "IC3") (pin "35") (pinfunction "RB11/AN11/PMA12/ERXERR/AETXERR_35") (pintype "bidirectional"))
      (node (ref "IC4") (pin "41") (pinfunction "RX_ER_41") (pintype "bidirectional"))
    )
    (net (code "15") (name "ETXD0") (class "Default")
      (node (ref "IC3") (pin "88") (pinfunction "C1TX/ETXD0/PMD10/RF1_88") (pintype "bidirectional"))
      (node (ref "IC4") (pin "3") (pinfunction "TXD_0_3") (pintype "bidirectional"))
    )
    (net (code "16") (name "ETXD1") (class "Default")
      (node (ref "IC3") (pin "87") (pinfunction "C1RX/ETXD1/PMD11/RF0_87") (pintype "bidirectional"))
      (node (ref "IC4") (pin "4") (pinfunction "TXD_1_4") (pintype "bidirectional"))
    )
    (net (code "17") (name "ETXEN") (class "Default")
      (node (ref "IC3") (pin "83") (pinfunction "ETXEN/CN15/PMD14/RD6_83") (pintype "bidirectional"))
      (node (ref "IC4") (pin "2") (pinfunction "TX_EN_2") (pintype "bidirectional"))
    )
    (net (code "18") (name "FLASH_CS") (class "Default")
      (node (ref "IC3") (pin "38") (pinfunction "RA1/TCK_38") (pintype "bidirectional"))
      (node (ref "R13") (pin "1") (pinfunction "1_1") (pintype "passive"))
      (node (ref "U$2") (pin "1") (pinfunction "~{CE}_1") (pintype "bidirectional"))
    )
    (net (code "19") (name "GND") (class "Default")
      (node (ref "C1") (pin "2") (pinfunction "2_2") (pintype "passive"))
      (node (ref "C10") (pin "2") (pinfunction "2_2") (pintype "passive"))
      (node (ref "C11") (pin "2") (pinfunction "2_2") (pintype "passive"))
      (node (ref "C12") (pin "-") (pinfunction "-_-") (pintype "passive"))
      (node (ref "C13") (pin "2") (pinfunction "2_2") (pintype "passive"))
      (node (ref "C14") (pin "2") (pinfunction "2_2") (pintype "passive"))
      (node (ref "C15") (pin "-") (pinfunction "-_-") (pintype "passive"))
      (node (ref "C16") (pin "2") (pinfunction "2_2") (pintype "passive"))
      (node (ref "C17") (pin "2") (pinfunction "2_2") (pintype "passive"))
      (node (ref "C18") (pin "2") (pinfunction "2_2") (pintype "passive"))
      (node (ref "C19") (pin "2") (pinfunction "2_2") (pintype "passive"))
      (node (ref "C2") (pin "2") (pinfunction "2_2") (pintype "passive"))
      (node (ref "C20") (pin "1") (pinfunction "1_1") (pintype "passive"))
      (node (ref "C21") (pin "2") (pinfunction "2_2") (pintype "passive"))
      (node (ref "C22") (pin "2") (pinfunction "2_2") (pintype "passive"))
      (node (ref "C23") (pin "1") (pinfunction "1_1") (pintype "passive"))
      (node (ref "C24") (pin "2") (pinfunction "2_2") (pintype "passive"))
      (node (ref "C25") (pin "2") (pinfunction "2_2") (pintype "passive"))
      (node (ref "C26") (pin "-") (pinfunction "-_-") (pintype "passive"))
      (node (ref "C27") (pin "2") (pinfunction "2_2") (pintype "passive"))
      (node (ref "C28") (pin "2") (pinfunction "2_2") (pintype "passive"))
      (node (ref "C29") (pin "2") (pinfunction "2_2") (pintype "passive"))
      (node (ref "C3") (pin "2") (pinfunction "2_2") (pintype "passive"))
      (node (ref "C30") (pin "-") (pinfunction "-_-") (pintype "passive"))
      (node (ref "C31") (pin "2") (pinfunction "2_2") (pintype "passive"))
      (node (ref "C32") (pin "2") (pinfunction "2_2") (pintype "passive"))
      (node (ref "C38") (pin "2") (pinfunction "2_2") (pintype "passive"))
      (node (ref "C4") (pin "2") (pinfunction "2_2") (pintype "passive"))
      (node (ref "C40") (pin "2") (pinfunction "2_2") (pintype "passive"))
      (node (ref "C41") (pin "2") (pinfunction "2_2") (pintype "passive"))
      (node (ref "C42") (pin "2") (pinfunction "2_2") (pintype "passive"))
      (node (ref "C45") (pin "2") (pinfunction "2_2") (pintype "passive"))
      (node (ref "C46") (pin "2") (pinfunction "2_2") (pintype "passive"))
      (node (ref "C47") (pin "2") (pinfunction "2_2") (pintype "passive"))
      (node (ref "C48") (pin "2") (pinfunction "2_2") (pintype "passive"))
      (node (ref "C49") (pin "2") (pinfunction "2_2") (pintype "passive"))
      (node (ref "C5") (pin "-") (pinfunction "-_-") (pintype "passive"))
      (node (ref "C50") (pin "2") (pinfunction "2_2") (pintype "passive"))
      (node (ref "C51") (pin "-") (pinfunction "-_-") (pintype "passive"))
      (node (ref "C52") (pin "-") (pinfunction "-_-") (pintype "passive"))
      (node (ref "C53") (pin "2") (pinfunction "2_2") (pintype "passive"))
      (node (ref "C54") (pin "2") (pinfunction "2_2") (pintype "passive"))
      (node (ref "C55") (pin "2") (pinfunction "2_2") (pintype "passive"))
      (node (ref "C56") (pin "2") (pinfunction "2_2") (pintype "passive"))
      (node (ref "C57") (pin "2") (pinfunction "2_2") (pintype "passive"))
      (node (ref "C59") (pin "2") (pinfunction "2_2") (pintype "passive"))
      (node (ref "C6") (pin "2") (pinfunction "2_2") (pintype "passive"))
      (node (ref "C7") (pin "2") (pinfunction "2_2") (pintype "passive"))
      (node (ref "C8") (pin "2") (pinfunction "2_2") (pintype "passive"))
      (node (ref "C9") (pin "2") (pinfunction "2_2") (pintype "passive"))
      (node (ref "IC1") (pin "2") (pinfunction "GND_2") (pintype "bidirectional"))
      (node (ref "IC2") (pin "1") (pinfunction "GND_1") (pintype "input"))
      (node (ref "IC3") (pin "15") (pinfunction "VSS_15") (pintype "power_in"))
      (node (ref "IC3") (pin "31") (pinfunction "AVSS_31") (pintype "bidirectional"))
      (node (ref "IC3") (pin "36") (pinfunction "VSS_36") (pintype "power_in"))
      (node (ref "IC3") (pin "45") (pinfunction "VSS_45") (pintype "power_in"))
      (node (ref "IC3") (pin "65") (pinfunction "VSS_65") (pintype "power_in"))
      (node (ref "IC3") (pin "75") (pinfunction "VSS_75") (pintype "power_in"))
      (node (ref "IC4") (pin "15") (pinfunction "CDVSS_15") (pintype "power_in"))
      (node (ref "IC4") (pin "19") (pinfunction "ANA18VSS_19") (pintype "power_in"))
      (node (ref "IC4") (pin "35") (pinfunction "IO_VSS2_35") (pintype "power_in"))
      (node (ref "IC4") (pin "36") (pinfunction "CORE_VSS_36") (pintype "power_in"))
      (node (ref "IC4") (pin "47") (pinfunction "IO_VSS1_47") (pintype "power_in"))
      (node (ref "IC4") (pin "6") (pinfunction "TXD_3_6") (pintype "bidirectional"))
      (node (ref "IC5") (pin "1") (pinfunction "GND_1") (pintype "input"))
      (node (ref "JP2") (pin "3") (pinfunction "3_3") (pintype "passive"))
      (node (ref "JP3") (pin "1") (pinfunction "1_1") (pintype "passive"))
      (node (ref "JP5") (pin "GND1") (pinfunction "GND_GND1") (pintype "bidirectional"))
      (node (ref "R21") (pin "1") (pinfunction "1_1") (pintype "passive"))
      (node (ref "R26") (pin "2") (pinfunction "2_2") (pintype "passive"))
      (node (ref "R27") (pin "2") (pinfunction "2_2") (pintype "passive"))
      (node (ref "R28") (pin "2") (pinfunction "2_2") (pintype "passive"))
      (node (ref "R29") (pin "2") (pinfunction "2_2") (pintype "passive"))
      (node (ref "R36") (pin "2") (pinfunction "2_2") (pintype "passive"))
      (node (ref "R6") (pin "2") (pinfunction "2_2") (pintype "passive"))
      (node (ref "RJ1") (pin "GND") (pinfunction "GND_GND") (pintype "bidirectional"))
      (node (ref "RJ1") (pin "SHIELD0") (pinfunction "SHIELD0_SHIELD0") (pintype "bidirectional"))
      (node (ref "RJ1") (pin "SHIELD1") (pinfunction "SHIELD1_SHIELD1") (pintype "bidirectional"))
      (node (ref "SV1") (pin "29") (pinfunction "29_29") (pintype "passive"))
      (node (ref "SV1") (pin "30") (pinfunction "30_30") (pintype "passive"))
      (node (ref "U$1") (pin "2") (pinfunction "GND_2") (pintype "power_in"))
      (node (ref "U$2") (pin "4") (pinfunction "VSS_4") (pintype "bidirectional"))
      (node (ref "U$7") (pin "2") (pinfunction "GND_2") (pintype "power_in"))
      (node (ref "U1") (pin "6") (pinfunction "GND_6") (pintype "bidirectional"))
      (node (ref "U1") (pin "CD2") (pinfunction "SHIELD_CD2") (pintype "bidirectional"))
      (node (ref "U1") (pin "GND1") (pinfunction "SHIELD_GND1") (pintype "bidirectional"))
      (node (ref "U1") (pin "GND2") (pinfunction "SHIELD_GND2") (pintype "bidirectional"))
      (node (ref "U2") (pin "16") (pinfunction "DGND1_16") (pintype "power_in"))
      (node (ref "U2") (pin "20") (pinfunction "DGND2_20") (pintype "power_in"))
      (node (ref "U2") (pin "21") (pinfunction "DGND3_21") (pintype "power_in"))
      (node (ref "U2") (pin "22") (pinfunction "DGND4_22") (pintype "power_in"))
      (node (ref "U2") (pin "4") (pinfunction "DGND_4") (pintype "power_in"))
      (node (ref "X3") (pin "4") (pinfunction "4_4") (pintype "passive"))
      (node (ref "X3") (pin "M1") (pinfunction "S1_M1") (pintype "passive"))
      (node (ref "X3") (pin "M2") (pinfunction "S2_M2") (pintype "passive"))
      (node (ref "Y3") (pin "2") (pinfunction "3_2") (pintype "passive"))
      (node (ref "Y3") (pin "4") (pinfunction "3_4") (pintype "passive"))
    )
    (net (code "20") (name "LED_ACT") (class "Default")
      (node (ref "IC4") (pin "26") (pinfunction "LED_ACTCOL_26") (pintype "bidirectional"))
      (node (ref "RJ1") (pin "G-") (pinfunction "G-_G-") (pintype "bidirectional"))
    )
    (net (code "21") (name "LED_LINK") (class "Default")
      (node (ref "IC4") (pin "28") (pinfunction "LED_LNK_28") (pintype "bidirectional"))
      (node (ref "RJ1") (pin "Y-") (pinfunction "Y-_Y-") (pintype "bidirectional"))
    )
    (net (code "22") (name "MCLR") (class "Default")
      (node (ref "C28") (pin "1") (pinfunction "1_1") (pintype "passive"))
      (node (ref "IC3") (pin "13") (pinfunction "MCLR_13") (pintype "bidirectional"))
      (node (ref "JP2") (pin "1") (pinfunction "1_1") (pintype "passive"))
      (node (ref "R9") (pin "1") (pinfunction "1_1") (pintype "passive"))
    )
    (net (code "23") (name "MISO") (class "Default")
      (node (ref "IC3") (pin "49") (pinfunction "SDA3A/SDI3A/U3ARX/PMA9/CN17/RF4_49") (pintype "bidirectional"))
      (node (ref "R16") (pin "1") (pinfunction "1_1") (pintype "passive"))
      (node (ref "U$2") (pin "2") (pinfunction "SO_2") (pintype "bidirectional"))
      (node (ref "U1") (pin "7") (pinfunction "DO_7") (pintype "bidirectional"))
    )
    (net (code "24") (name "MOSI") (class "Default")
      (node (ref "IC3") (pin "50") (pinfunction "SCL3A/SDO3A/U3ATX/PMA8/CN18/RF5_50") (pintype "bidirectional"))
      (node (ref "U$2") (pin "5") (pinfunction "SI_5") (pintype "bidirectional"))
      (node (ref "U1") (pin "3") (pinfunction "DI_3") (pintype "bidirectional"))
    )
    (net (code "25") (name "Net-(C36-Pad2)") (class "Default")
      (node (ref "C36") (pin "2") (pinfunction "2_2") (pintype "passive"))
      (node (ref "R23") (pin "1") (pinfunction "1_1") (pintype "passive"))
    )
    (net (code "26") (name "Net-(C37-Pad2)") (class "Default")
      (node (ref "C37") (pin "2") (pinfunction "2_2") (pintype "passive"))
      (node (ref "R24") (pin "1") (pinfunction "1_1") (pintype "passive"))
    )
    (net (code "27") (name "Net-(C39-Pad2)") (class "Default")
      (node (ref "C39") (pin "2") (pinfunction "2_2") (pintype "passive"))
      (node (ref "R22") (pin "1") (pinfunction "1_1") (pintype "passive"))
    )
    (net (code "28") (name "Net-(C43-Pad1)") (class "Default")
      (node (ref "C43") (pin "1") (pinfunction "1_1") (pintype "passive"))
      (node (ref "R31") (pin "1") (pinfunction "1_1") (pintype "passive"))
    )
    (net (code "29") (name "Net-(C44-Pad1)") (class "Default")
      (node (ref "C44") (pin "1") (pinfunction "1_1") (pintype "passive"))
      (node (ref "R32") (pin "1") (pinfunction "1_1") (pintype "passive"))
    )
    (net (code "30") (name "Net-(IC1-I{slash}O_1)") (class "Default")
      (node (ref "IC1") (pin "1") (pinfunction "I/O_1_1") (pintype "bidirectional"))
      (node (ref "X3") (pin "2") (pinfunction "2_2") (pintype "passive"))
    )
    (net (code "31") (name "Net-(IC1-I{slash}O_2)") (class "Default")
      (node (ref "IC1") (pin "3") (pinfunction "I/O_2_3") (pintype "bidirectional"))
      (node (ref "X3") (pin "3") (pinfunction "3_3") (pintype "passive"))
    )
    (net (code "32") (name "Net-(IC3-OSC1{slash}CLKI{slash}RC12)") (class "Default")
      (node (ref "IC3") (pin "63") (pinfunction "OSC1/CLKI/RC12_63") (pintype "bidirectional"))
      (node (ref "U$1") (pin "3") (pinfunction "OUT_3") (pintype "output"))
    )
    (net (code "33") (name "Net-(IC3-RC13{slash}CN1{slash}SOSCI)") (class "Default")
      (node (ref "C20") (pin "2") (pinfunction "2_2") (pintype "passive"))
      (node (ref "IC3") (pin "73") (pinfunction "RC13/CN1/SOSCI_73") (pintype "bidirectional"))
      (node (ref "X2") (pin "1") (pinfunction "1_1") (pintype "passive"))
    )
    (net (code "34") (name "Net-(IC3-RC14{slash}CN0{slash}SOSCO{slash}T1CK)") (class "Default")
      (node (ref "C23") (pin "2") (pinfunction "2_2") (pintype "passive"))
      (node (ref "IC3") (pin "74") (pinfunction "RC14/CN0/SOSCO/T1CK_74") (pintype "bidirectional"))
      (node (ref "X2") (pin "2") (pinfunction "2_2") (pintype "passive"))
    )
    (net (code "35") (name "Net-(IC3-VDDCORE)") (class "Default")
      (node (ref "C10") (pin "1") (pinfunction "1_1") (pintype "passive"))
      (node (ref "IC3") (pin "85") (pinfunction "VDDCORE_85") (pintype "bidirectional"))
    )
    (net (code "36") (name "Net-(IC4-IP_PH_M)") (class "Default")
      (node (ref "IC4") (pin "20") (pinfunction "IP_PH_M_20") (pintype "input"))
      (node (ref "R10") (pin "1") (pinfunction "1_1") (pintype "passive"))
    )
    (net (code "37") (name "Net-(IC4-IP_PH_P)") (class "Default")
      (node (ref "IC4") (pin "21") (pinfunction "IP_PH_P_21") (pintype "input"))
      (node (ref "R7") (pin "1") (pinfunction "1_1") (pintype "passive"))
    )
    (net (code "38") (name "Net-(IC4-RX_DV)") (class "Default")
      (node (ref "IC4") (pin "39") (pinfunction "RX_DV_39") (pintype "bidirectional"))
      (node (ref "R20") (pin "2") (pinfunction "2_2") (pintype "passive"))
    )
    (net (code "39") (name "Net-(IC4-VREF)") (class "Default")
      (node (ref "IC4") (pin "24") (pinfunction "VREF_24") (pintype "bidirectional"))
      (node (ref "R6") (pin "1") (pinfunction "1_1") (pintype "passive"))
    )
    (net (code "40") (name "Net-(JP1-LEFT)") (class "Default")
      (node (ref "C43") (pin "2") (pinfunction "2_2") (pintype "passive"))
      (node (ref "JP1") (pin "TIP") (pinfunction "LEFT_TIP") (pintype "bidirectional"))
      (node (ref "R34") (pin "1") (pinfunction "1_1") (pintype "passive"))
    )
    (net (code "41") (name "Net-(JP1-RIGHT)") (class "Default")
      (node (ref "C44") (pin "2") (pinfunction "2_2") (pintype "passive"))
      (node (ref "JP1") (pin "RING") (pinfunction "RIGHT_RING") (pintype "bidirectional"))
      (node (ref "R33") (pin "1") (pinfunction "1_1") (pintype "passive"))
    )
    (net (code "42") (name "Net-(JP5-VCC)") (class "Default")
      (node (ref "F1") (pin "1") (pinfunction "1_1") (pintype "passive"))
      (node (ref "JP5") (pin "VBUS1") (pinfunction "VCC_VBUS1") (pintype "bidirectional"))
    )
    (net (code "43") (name "Net-(R42-Pad2)") (class "Default")
      (node (ref "R42") (pin "2") (pinfunction "2_2") (pintype "passive"))
      (node (ref "RJ1") (pin "G+") (pinfunction "G+_G+") (pintype "bidirectional"))
    )
    (net (code "44") (name "Net-(R43-Pad1)") (class "Default")
      (node (ref "R43") (pin "1") (pinfunction "1_1") (pintype "passive"))
      (node (ref "RJ1") (pin "Y+") (pinfunction "Y+_Y+") (pintype "bidirectional"))
    )
    (net (code "45") (name "Net-(U2A-GBUF)") (class "Default")
      (node (ref "R23") (pin "2") (pinfunction "2_2") (pintype "passive"))
      (node (ref "U2") (pin "42") (pinfunction "GBUF_42") (pintype "bidirectional"))
    )
    (net (code "46") (name "Net-(U2A-GPIO0)") (class "Default")
      (node (ref "R26") (pin "1") (pinfunction "1_1") (pintype "passive"))
      (node (ref "U2") (pin "33") (pinfunction "GPIO0_33") (pintype "bidirectional"))
    )
    (net (code "47") (name "Net-(U2A-GPIO1)") (class "Default")
      (node (ref "R27") (pin "1") (pinfunction "1_1") (pintype "passive"))
      (node (ref "U2") (pin "34") (pinfunction "GPIO1_34") (pintype "bidirectional"))
    )
    (net (code "48") (name "Net-(U2A-GPIO2{slash}DCLK)") (class "Default")
      (node (ref "R28") (pin "1") (pinfunction "1_1") (pintype "passive"))
      (node (ref "U2") (pin "9") (pinfunction "GPIO2/DCLK_9") (pintype "bidirectional"))
    )
    (net (code "49") (name "Net-(U2A-GPIO3{slash}SDATA)") (class "Default")
      (node (ref "R29") (pin "1") (pinfunction "1_1") (pintype "passive"))
      (node (ref "U2") (pin "10") (pinfunction "GPIO3/SDATA_10") (pintype "bidirectional"))
    )
    (net (code "50") (name "Net-(U2A-LEFT)") (class "Default")
      (node (ref "R22") (pin "2") (pinfunction "2_2") (pintype "passive"))
      (node (ref "R31") (pin "2") (pinfunction "2_2") (pintype "passive"))
      (node (ref "U2") (pin "46") (pinfunction "LEFT_46") (pintype "bidirectional"))
    )
    (net (code "51") (name "Net-(U2A-RCAP)") (class "Default")
      (node (ref "R25") (pin "2") (pinfunction "2_2") (pintype "passive"))
      (node (ref "U2") (pin "44") (pinfunction "RCAP_44") (pintype "bidirectional"))
    )
    (net (code "52") (name "Net-(U2A-RIGHT)") (class "Default")
      (node (ref "R24") (pin "2") (pinfunction "2_2") (pintype "passive"))
      (node (ref "R32") (pin "2") (pinfunction "2_2") (pintype "passive"))
      (node (ref "U2") (pin "39") (pinfunction "RIGHT_39") (pintype "bidirectional"))
    )
    (net (code "53") (name "Net-(U2A-RX)") (class "Default")
      (node (ref "R30") (pin "1") (pinfunction "1_1") (pintype "passive"))
      (node (ref "U2") (pin "26") (pinfunction "RX_26") (pintype "bidirectional"))
    )
    (net (code "54") (name "Net-(U2A-XTALI)") (class "Default")
      (node (ref "C50") (pin "1") (pinfunction "1_1") (pintype "passive"))
      (node (ref "R35") (pin "2") (pinfunction "2_2") (pintype "passive"))
      (node (ref "U2") (pin "18") (pinfunction "XTALI_18") (pintype "bidirectional"))
      (node (ref "Y3") (pin "1") (pinfunction "2_1") (pintype "passive"))
    )
    (net (code "55") (name "Net-(U2A-XTALO)") (class "Default")
      (node (ref "C49") (pin "1") (pinfunction "1_1") (pintype "passive"))
      (node (ref "R35") (pin "1") (pinfunction "1_1") (pintype "passive"))
      (node (ref "U2") (pin "17") (pinfunction "XTALO_17") (pintype "bidirectional"))
      (node (ref "Y3") (pin "3") (pinfunction "1_3") (pintype "passive"))
    )
    (net (code "56") (name "PGEC") (class "Default")
      (node (ref "IC3") (pin "24") (pinfunction "RB1/AN1/CN3/PGC1_24") (pintype "bidirectional"))
      (node (ref "JP2") (pin "5") (pinfunction "5_5") (pintype "passive"))
    )
    (net (code "57") (name "PGED") (class "Default")
      (node (ref "IC3") (pin "25") (pinfunction "RB0/AN0/CN2/PGD1_25") (pintype "bidirectional"))
      (node (ref "JP2") (pin "4") (pinfunction "4_4") (pintype "passive"))
    )
    (net (code "58") (name "RA6") (class "Default")
      (node (ref "IC3") (pin "91") (pinfunction "RA6/TRCLK_91") (pintype "bidirectional"))
      (node (ref "SV1") (pin "17") (pinfunction "17_17") (pintype "passive"))
    )
    (net (code "59") (name "RA7") (class "Default")
      (node (ref "IC3") (pin "92") (pinfunction "RA7/TRD3_92") (pintype "bidirectional"))
      (node (ref "SV1") (pin "20") (pinfunction "20_20") (pintype "passive"))
    )
    (net (code "60") (name "RC3") (class "Default")
      (node (ref "IC3") (pin "8") (pinfunction "RC3/T4CK/AC2RX_8") (pintype "bidirectional"))
    )
    (net (code "61") (name "RC15") (class "Default")
      (node (ref "IC3") (pin "64") (pinfunction "OSC2/CLKO/RC15_64") (pintype "bidirectional"))
      (node (ref "SV1") (pin "4") (pinfunction "4_4") (pintype "passive"))
    )
    (net (code "62") (name "RD1") (class "Default")
      (node (ref "IC3") (pin "76") (pinfunction "OC2/RD1_76") (pintype "bidirectional"))
      (node (ref "SV1") (pin "7") (pinfunction "7_7") (pintype "passive"))
    )
    (net (code "63") (name "RD2") (class "Default")
      (node (ref "IC3") (pin "77") (pinfunction "OC3/RD2_77") (pintype "bidirectional"))
      (node (ref "SV1") (pin "10") (pinfunction "10_10") (pintype "passive"))
    )
    (net (code "64") (name "RD3") (class "Default")
      (node (ref "IC3") (pin "78") (pinfunction "OC4/RD3_78") (pintype "bidirectional"))
      (node (ref "SV1") (pin "9") (pinfunction "9_9") (pintype "passive"))
    )
    (net (code "65") (name "RD4") (class "Default")
      (node (ref "IC3") (pin "81") (pinfunction "PMWR/CN13/OC5/RD4_81") (pintype "bidirectional"))
      (node (ref "SV1") (pin "14") (pinfunction "14_14") (pintype "passive"))
    )
    (net (code "66") (name "RD5") (class "Default")
      (node (ref "IC3") (pin "82") (pinfunction "CN14/PMRD/RD5_82") (pintype "bidirectional"))
      (node (ref "SV1") (pin "13") (pinfunction "13_13") (pintype "passive"))
    )
    (net (code "67") (name "RD7") (class "Default")
      (node (ref "IC3") (pin "84") (pinfunction "ETXCLK/CN16/PMD15/RD7_84") (pintype "bidirectional"))
      (node (ref "SV1") (pin "16") (pinfunction "16_16") (pintype "passive"))
    )
    (net (code "68") (name "RD9") (class "Default")
      (node (ref "IC3") (pin "69") (pinfunction "SS1/IC2/RD9_69") (pintype "bidirectional"))
      (node (ref "SV1") (pin "5") (pinfunction "5_5") (pintype "passive"))
    )
    (net (code "69") (name "RD12") (class "Default")
      (node (ref "IC3") (pin "79") (pinfunction "ETXD2/IC5/PMD12/RD12_79") (pintype "bidirectional"))
      (node (ref "SV1") (pin "12") (pinfunction "12_12") (pintype "passive"))
    )
    (net (code "70") (name "RD13") (class "Default")
      (node (ref "IC3") (pin "80") (pinfunction "ETXD3/CN19/PMD13/RD13_80") (pintype "bidirectional"))
      (node (ref "SV1") (pin "11") (pinfunction "11_11") (pintype "passive"))
    )
    (net (code "71") (name "RD_N") (class "Default")
      (node (ref "IC4") (pin "13") (pinfunction "TPRDM_13") (pintype "bidirectional"))
      (node (ref "R5") (pin "1") (pinfunction "1_1") (pintype "passive"))
      (node (ref "RJ1") (pin "RD-") (pinfunction "RD-_RD-") (pintype "bidirectional"))
    )
    (net (code "72") (name "RD_P") (class "Default")
      (node (ref "IC4") (pin "14") (pinfunction "TPRDP_14") (pintype "bidirectional"))
      (node (ref "R4") (pin "1") (pinfunction "1_1") (pintype "passive"))
      (node (ref "RJ1") (pin "RD+") (pinfunction "RD+_RD+") (pintype "bidirectional"))
    )
    (net (code "73") (name "RE0") (class "Default")
      (node (ref "IC3") (pin "93") (pinfunction "RE0/PMD0_93") (pintype "bidirectional"))
      (node (ref "SV1") (pin "19") (pinfunction "19_19") (pintype "passive"))
    )
    (net (code "74") (name "RE1") (class "Default")
      (node (ref "IC3") (pin "94") (pinfunction "RE1/PMD1_94") (pintype "bidirectional"))
      (node (ref "SV1") (pin "22") (pinfunction "22_22") (pintype "passive"))
    )
    (net (code "75") (name "RE2") (class "Default")
      (node (ref "IC3") (pin "98") (pinfunction "RE2/PMD2_98") (pintype "bidirectional"))
      (node (ref "SV1") (pin "26") (pinfunction "26_26") (pintype "passive"))
    )
    (net (code "76") (name "RE3") (class "Default")
      (node (ref "IC3") (pin "99") (pinfunction "RE3/PMD3_99") (pintype "bidirectional"))
      (node (ref "SV1") (pin "25") (pinfunction "25_25") (pintype "passive"))
    )
    (net (code "77") (name "RE4") (class "Default")
      (node (ref "IC3") (pin "100") (pinfunction "RE4/PMD4_100") (pintype "bidirectional"))
      (node (ref "SV1") (pin "28") (pinfunction "28_28") (pintype "passive"))
    )
    (net (code "78") (name "RE5") (class "Default")
      (node (ref "IC3") (pin "3") (pinfunction "RE5/PMD5_3") (pintype "bidirectional"))
      (node (ref "SV1") (pin "27") (pinfunction "27_27") (pintype "passive"))
    )
    (net (code "79") (name "REG_OUT") (class "Default")
      (node (ref "C18") (pin "1") (pinfunction "1_1") (pintype "passive"))
      (node (ref "C19") (pin "1") (pinfunction "1_1") (pintype "passive"))
      (node (ref "C24") (pin "1") (pinfunction "1_1") (pintype "passive"))
      (node (ref "C32") (pin "1") (pinfunction "1_1") (pintype "passive"))
      (node (ref "IC4") (pin "18") (pinfunction "ANA18VDD_18") (pintype "power_in"))
      (node (ref "IC4") (pin "23") (pinfunction "REG_OUT_23") (pintype "output"))
      (node (ref "IC4") (pin "37") (pinfunction "CORE_VDD_37") (pintype "power_in"))
    )
    (net (code "80") (name "RF2_ROT_SW") (class "Default")
      (node (ref "IC3") (pin "52") (pinfunction "SDA1A/SDI1A/U1ARX/RF2_52") (pintype "bidirectional"))
      (node (ref "SV1") (pin "2") (pinfunction "2_2") (pintype "passive"))
    )
    (net (code "81") (name "RF8") (class "Default")
      (node (ref "IC3") (pin "53") (pinfunction "SCL1A/SDO1A/U1ATX/RF8_53") (pintype "bidirectional"))
      (node (ref "SV1") (pin "1") (pinfunction "1_1") (pintype "passive"))
    )
    (net (code "82") (name "RG0") (class "Default")
      (node (ref "IC3") (pin "90") (pinfunction "C2RX/PMD8/RG0_90") (pintype "bidirectional"))
      (node (ref "SV1") (pin "18") (pinfunction "18_18") (pintype "passive"))
    )
    (net (code "83") (name "RG1") (class "Default")
      (node (ref "IC3") (pin "89") (pinfunction "C2TX/ETXERR/PMD9/RG1_89") (pintype "bidirectional"))
      (node (ref "SV1") (pin "15") (pinfunction "15_15") (pintype "passive"))
    )
    (net (code "84") (name "RG6") (class "Default")
      (node (ref "IC3") (pin "10") (pinfunction "ECOL/U2BTX/U2ARTS/PMA5/CN8/SCK2/RG6_10") (pintype "bidirectional"))
    )
    (net (code "85") (name "RG7_SDA2A") (class "Default")
      (node (ref "IC3") (pin "11") (pinfunction "ECRS/SDA2A/U2ARX/PMA4/CN9/SDI2A/RG7_11") (pintype "bidirectional"))
    )
    (net (code "86") (name "RG12") (class "Default")
      (node (ref "IC3") (pin "96") (pinfunction "TRD1/RG12_96") (pintype "bidirectional"))
      (node (ref "SV1") (pin "24") (pinfunction "24_24") (pintype "passive"))
    )
    (net (code "87") (name "RG13") (class "Default")
      (node (ref "IC3") (pin "97") (pinfunction "TRD0/RG13_97") (pintype "bidirectional"))
      (node (ref "SV1") (pin "23") (pinfunction "23_23") (pintype "passive"))
    )
    (net (code "88") (name "RG14") (class "Default")
      (node (ref "IC3") (pin "95") (pinfunction "TRD2/RG14_95") (pintype "bidirectional"))
      (node (ref "SV1") (pin "21") (pinfunction "21_21") (pintype "passive"))
    )
    (net (code "89") (name "RG15") (class "Default")
      (node (ref "IC3") (pin "1") (pinfunction "AERXERR/RG15_1") (pintype "bidirectional"))
    )
    (net (code "90") (name "RXD") (class "Default")
      (node (ref "IC3") (pin "47") (pinfunction "AETXD0/SS1A/U1BRX/U1ACTS/CN20/RD14_47") (pintype "bidirectional"))
      (node (ref "JP3") (pin "3") (pinfunction "3_3") (pintype "passive"))
    )
    (net (code "91") (name "SCK") (class "Default")
      (node (ref "IC3") (pin "39") (pinfunction "AC1TX/SCK3A/U3BTX/U3ARTS/RF13_39") (pintype "bidirectional"))
      (node (ref "U$2") (pin "6") (pinfunction "SCK_6") (pintype "bidirectional"))
      (node (ref "U1") (pin "5") (pinfunction "SCK_5") (pintype "bidirectional"))
    )
    (net (code "92") (name "SCL1") (class "Default")
      (node (ref "IC3") (pin "66") (pinfunction "RA14/INT3/SCL1/AETXCLK_66") (pintype "bidirectional"))
      (node (ref "SV1") (pin "3") (pinfunction "3_3") (pintype "passive"))
    )
    (net (code "93") (name "SDA1") (class "Default")
      (node (ref "IC3") (pin "67") (pinfunction "RA15/INT4/SDA1/AETXEN_67") (pintype "bidirectional"))
      (node (ref "SV1") (pin "6") (pinfunction "6_6") (pintype "passive"))
    )
    (net (code "94") (name "SD_CS") (class "Default")
      (node (ref "IC3") (pin "44") (pinfunction "RB15/AN15/CN12/OCFB/_44") (pintype "bidirectional"))
      (node (ref "R11") (pin "1") (pinfunction "1_1") (pintype "passive"))
      (node (ref "U1") (pin "2") (pinfunction "CS_2") (pintype "bidirectional"))
    )
    (net (code "95") (name "SD_PRESENT") (class "Default")
      (node (ref "IC3") (pin "51") (pinfunction "USBID/RF3_51") (pintype "bidirectional"))
      (node (ref "R8") (pin "1") (pinfunction "1_1") (pintype "passive"))
      (node (ref "U1") (pin "CD1") (pinfunction "SHIELD_CD1") (pintype "bidirectional"))
    )
    (net (code "96") (name "TD_N") (class "Default")
      (node (ref "IC4") (pin "16") (pinfunction "TPTDM_16") (pintype "bidirectional"))
      (node (ref "R3") (pin "1") (pinfunction "1_1") (pintype "passive"))
      (node (ref "RJ1") (pin "TD-") (pinfunction "TD-_TD-") (pintype "bidirectional"))
    )
    (net (code "97") (name "TD_P") (class "Default")
      (node (ref "IC4") (pin "17") (pinfunction "TPTDP_17") (pintype "bidirectional"))
      (node (ref "R2") (pin "1") (pinfunction "1_1") (pintype "passive"))
      (node (ref "RJ1") (pin "TD+") (pinfunction "TD+_TD+") (pintype "bidirectional"))
    )
    (net (code "98") (name "TXD") (class "Default")
      (node (ref "IC3") (pin "48") (pinfunction "AETXD1/SCK1A/U1BTX/U1ARTS/CN21/BCLK1/RD15_48") (pintype "bidirectional"))
      (node (ref "JP3") (pin "2") (pinfunction "2_2") (pintype "passive"))
    )
    (net (code "99") (name "VBUS") (class "Default")
      (node (ref "C12") (pin "+") (pinfunction "+_+") (pintype "passive"))
      (node (ref "C13") (pin "1") (pinfunction "1_1") (pintype "passive"))
      (node (ref "C27") (pin "1") (pinfunction "1_1") (pintype "passive"))
      (node (ref "C30") (pin "+") (pinfunction "+_+") (pintype "passive"))
      (node (ref "C5") (pin "+") (pinfunction "+_+") (pintype "passive"))
      (node (ref "C52") (pin "+") (pinfunction "+_+") (pintype "passive"))
      (node (ref "C53") (pin "1") (pinfunction "1_1") (pintype "passive"))
      (node (ref "F1") (pin "2") (pinfunction "2_2") (pintype "passive"))
      (node (ref "IC1") (pin "5") (pinfunction "VBUS_5") (pintype "bidirectional"))
      (node (ref "IC2") (pin "3") (pinfunction "IN_3") (pintype "input"))
      (node (ref "IC3") (pin "54") (pinfunction "VBUS_54") (pintype "bidirectional"))
      (node (ref "IC5") (pin "3") (pinfunction "IN_3") (pintype "input"))
      (node (ref "SV1") (pin "31") (pinfunction "31_31") (pintype "passive"))
      (node (ref "SV1") (pin "32") (pinfunction "32_32") (pintype "passive"))
      (node (ref "X3") (pin "1") (pinfunction "1_1") (pintype "passive"))
    )
    (net (code "100") (name "VS_AGND") (class "Default")
      (node (ref "C33") (pin "2") (pinfunction "2_2") (pintype "passive"))
      (node (ref "C34") (pin "2") (pinfunction "2_2") (pintype "passive"))
      (node (ref "C35") (pin "2") (pinfunction "2_2") (pintype "passive"))
      (node (ref "C36") (pin "1") (pinfunction "1_1") (pintype "passive"))
      (node (ref "C37") (pin "1") (pinfunction "1_1") (pintype "passive"))
      (node (ref "C39") (pin "1") (pinfunction "1_1") (pintype "passive"))
      (node (ref "C58") (pin "2") (pinfunction "2_2") (pintype "passive"))
      (node (ref "JP1") (pin "SLEEVE") (pinfunction "SLEEVE_SLEEVE") (pintype "bidirectional"))
      (node (ref "R21") (pin "2") (pinfunction "2_2") (pintype "passive"))
      (node (ref "R25") (pin "1") (pinfunction "1_1") (pintype "passive"))
      (node (ref "R33") (pin "2") (pinfunction "2_2") (pintype "passive"))
      (node (ref "R34") (pin "2") (pinfunction "2_2") (pintype "passive"))
      (node (ref "U2") (pin "37") (pinfunction "AGND_37") (pintype "power_in"))
      (node (ref "U2") (pin "40") (pinfunction "AGND1_40") (pintype "power_in"))
      (node (ref "U2") (pin "41") (pinfunction "AGND2_41") (pintype "power_in"))
      (node (ref "U2") (pin "47") (pinfunction "AGND3_47") (pintype "power_in"))
    )
    (net (code "101") (name "VS_AVDD") (class "Default")
      (node (ref "C33") (pin "1") (pinfunction "1_1") (pintype "passive"))
      (node (ref "C34") (pin "1") (pinfunction "1_1") (pintype "passive"))
      (node (ref "C35") (pin "1") (pinfunction "1_1") (pintype "passive"))
      (node (ref "C58") (pin "1") (pinfunction "1_1") (pintype "passive"))
      (node (ref "L1") (pin "1") (pinfunction "1_1") (pintype "passive"))
      (node (ref "U2") (pin "38") (pinfunction "AVDD_38") (pintype "power_in"))
      (node (ref "U2") (pin "43") (pinfunction "AVDD1_43") (pintype "power_in"))
      (node (ref "U2") (pin "45") (pinfunction "AVDD2_45") (pintype "power_in"))
    )
    (net (code "102") (name "VS_CVDD") (class "Default")
      (node (ref "C45") (pin "1") (pinfunction "1_1") (pintype "passive"))
      (node (ref "C46") (pin "1") (pinfunction "1_1") (pintype "passive"))
      (node (ref "C47") (pin "1") (pinfunction "1_1") (pintype "passive"))
      (node (ref "C48") (pin "1") (pinfunction "1_1") (pintype "passive"))
      (node (ref "C57") (pin "1") (pinfunction "1_1") (pintype "passive"))
      (node (ref "L2") (pin "1") (pinfunction "1_1") (pintype "passive"))
      (node (ref "U2") (pin "24") (pinfunction "CVDD2_24") (pintype "power_in"))
      (node (ref "U2") (pin "31") (pinfunction "CVDD3_31") (pintype "power_in"))
      (node (ref "U2") (pin "5") (pinfunction "CVDD_5") (pintype "power_in"))
      (node (ref "U2") (pin "7") (pinfunction "CVDD1_7") (pintype "power_in"))
    )
    (net (code "103") (name "VS_DREQ") (class "Default")
      (node (ref "IC3") (pin "6") (pinfunction "RC1/T2CK_6") (pintype "bidirectional"))
      (node (ref "U2") (pin "8") (pinfunction "DREQ_8") (pintype "bidirectional"))
    )
    (net (code "104") (name "VS_MISO") (class "Default")
      (node (ref "IC3") (pin "9") (pinfunction "RC4/T5CK/SDI1_9") (pintype "bidirectional"))
      (node (ref "U2") (pin "30") (pinfunction "SO_30") (pintype "bidirectional"))
    )
    (net (code "105") (name "VS_MOSI") (class "Default")
      (node (ref "IC3") (pin "72") (pinfunction "SDO1/INT0/OC1/RD0_72") (pintype "bidirectional"))
      (node (ref "U2") (pin "29") (pinfunction "SI_29") (pintype "bidirectional"))
    )
    (net (code "106") (name "VS_SCK") (class "Default")
      (node (ref "IC3") (pin "70") (pinfunction "SCKI/IC3/PMCS2/PMA15/RD10_70") (pintype "bidirectional"))
      (node (ref "U2") (pin "28") (pinfunction "SCLK_28") (pintype "bidirectional"))
    )
    (net (code "107") (name "VS_XCS") (class "Default")
      (node (ref "IC3") (pin "5") (pinfunction "RE7/PMD7_5") (pintype "bidirectional"))
      (node (ref "U2") (pin "23") (pinfunction "XCS_23") (pintype "bidirectional"))
    )
    (net (code "108") (name "VS_XDCS") (class "Default")
      (node (ref "IC3") (pin "4") (pinfunction "RE6/PMD6_4") (pintype "bidirectional"))
      (node (ref "U2") (pin "13") (pinfunction "XDCS/BSYNC_13") (pintype "bidirectional"))
    )
    (net (code "109") (name "VS_XRST") (class "Default")
      (node (ref "IC3") (pin "7") (pinfunction "RC2/T3CK/AC2TX_7") (pintype "bidirectional"))
      (node (ref "R36") (pin "1") (pinfunction "1_1") (pintype "passive"))
      (node (ref "U2") (pin "3") (pinfunction "XRESET_3") (pintype "bidirectional"))
    )
    (net (code "110") (name "_2V6") (class "Default")
      (node (ref "C51") (pin "+") (pinfunction "+_+") (pintype "passive"))
      (node (ref "C54") (pin "1") (pinfunction "1_1") (pintype "passive"))
      (node (ref "IC5") (pin "2") (pinfunction "OUT_2") (pintype "passive"))
      (node (ref "IC5") (pin "TAB") (pinfunction "OUT1_TAB") (pintype "passive"))
      (node (ref "L1") (pin "2") (pinfunction "2_2") (pintype "passive"))
      (node (ref "L2") (pin "2") (pinfunction "2_2") (pintype "passive"))
    )
    (net (code "111") (name "unconnected-(IC3-AC1RX{slash}SS3A{slash}U3BRX{slash}U3ACTS{slash}RF12-Pad40)") (class "Default")
      (node (ref "IC3") (pin "40") (pinfunction "AC1RX/SS3A/U3BRX/U3ACTS/RF12_40") (pintype "bidirectional"))
    )
    (net (code "112") (name "unconnected-(IC3-RA0{slash}TMS-Pad17)") (class "Default")
      (node (ref "IC3") (pin "17") (pinfunction "RA0/TMS_17") (pintype "bidirectional"))
    )
    (net (code "113") (name "unconnected-(IC3-RA2{slash}SCL2-Pad58)") (class "Default")
      (node (ref "IC3") (pin "58") (pinfunction "RA2/SCL2_58") (pintype "bidirectional"))
    )
    (net (code "114") (name "unconnected-(IC3-RA3{slash}SDA2-Pad59)") (class "Default")
      (node (ref "IC3") (pin "59") (pinfunction "RA3/SDA2_59") (pintype "bidirectional"))
    )
    (net (code "115") (name "unconnected-(IC3-RA4{slash}TDI-Pad60)") (class "Default")
      (node (ref "IC3") (pin "60") (pinfunction "RA4/TDI_60") (pintype "bidirectional"))
    )
    (net (code "116") (name "unconnected-(IC3-RA5{slash}TDO-Pad61)") (class "Default")
      (node (ref "IC3") (pin "61") (pinfunction "RA5/TDO_61") (pintype "bidirectional"))
    )
    (net (code "117") (name "unconnected-(IC3-RA9{slash}VR-{slash}PMA7{slash}CVREF-{slash}AERXD2-Pad28)") (class "Default")
      (node (ref "IC3") (pin "28") (pinfunction "RA9/VR-/PMA7/CVREF-/AERXD2_28") (pintype "bidirectional"))
    )
    (net (code "118") (name "unconnected-(IC3-RA10{slash}VR+{slash}CVREF+{slash}AERXD3{slash}PMA6-Pad29)") (class "Default")
      (node (ref "IC3") (pin "29") (pinfunction "RA10/VR+/CVREF+/AERXD3/PMA6_29") (pintype "bidirectional"))
    )
    (net (code "119") (name "unconnected-(IC3-RB2{slash}AN2{slash}CN4{slash}C2IN--Pad23)") (class "Default")
      (node (ref "IC3") (pin "23") (pinfunction "RB2/AN2/CN4/C2IN-_23") (pintype "bidirectional"))
    )
    (net (code "120") (name "unconnected-(IC3-RB3{slash}AN3{slash}CN5{slash}C2IN+-Pad22)") (class "Default")
      (node (ref "IC3") (pin "22") (pinfunction "RB3/AN3/CN5/C2IN+_22") (pintype "bidirectional"))
    )
    (net (code "121") (name "unconnected-(IC3-RB4{slash}AN4{slash}CN6{slash}C1IN--Pad21)") (class "Default")
      (node (ref "IC3") (pin "21") (pinfunction "RB4/AN4/CN6/C1IN-_21") (pintype "bidirectional"))
    )
    (net (code "122") (name "unconnected-(IC3-RB5{slash}AN5{slash}CN7{slash}C1IN+{slash}VBUSON-Pad20)") (class "Default")
      (node (ref "IC3") (pin "20") (pinfunction "RB5/AN5/CN7/C1IN+/VBUSON_20") (pintype "bidirectional"))
    )
    (net (code "123") (name "unconnected-(IC3-RB6{slash}AN6{slash}PGC2{slash}OCFA-Pad26)") (class "Default")
      (node (ref "IC3") (pin "26") (pinfunction "RB6/AN6/PGC2/OCFA_26") (pintype "bidirectional"))
    )
    (net (code "124") (name "unconnected-(IC3-RB7{slash}AN7{slash}PGD2-Pad27)") (class "Default")
      (node (ref "IC3") (pin "27") (pinfunction "RB7/AN7/PGD2_27") (pintype "bidirectional"))
    )
    (net (code "125") (name "unconnected-(IC3-RB8{slash}AN8{slash}C1OUT-Pad32)") (class "Default")
      (node (ref "IC3") (pin "32") (pinfunction "RB8/AN8/C1OUT_32") (pintype "bidirectional"))
    )
    (net (code "126") (name "unconnected-(IC3-RB9{slash}AN9{slash}C2OUT-Pad33)") (class "Default")
      (node (ref "IC3") (pin "33") (pinfunction "RB9/AN9/C2OUT_33") (pintype "bidirectional"))
    )
    (net (code "127") (name "unconnected-(IC3-RB14{slash}AN14{slash}PMA1{slash}ERXD2{slash}AETXD3{slash}-Pad43)") (class "Default")
      (node (ref "IC3") (pin "43") (pinfunction "RB14/AN14/PMA1/ERXD2/AETXD3/_43") (pintype "bidirectional"))
    )
    (net (code "128") (name "unconnected-(IC3-RE8{slash}INT1{slash}AERXD0-Pad18)") (class "Default")
      (node (ref "IC3") (pin "18") (pinfunction "RE8/INT1/AERXD0_18") (pintype "bidirectional"))
    )
    (net (code "129") (name "unconnected-(IC3-RE9{slash}INT2{slash}AERXD1-Pad19)") (class "Default")
      (node (ref "IC3") (pin "19") (pinfunction "RE9/INT2/AERXD1_19") (pintype "bidirectional"))
    )
    (net (code "130") (name "unconnected-(IC4-CLK2MAC-Pad25)") (class "Default")
      (node (ref "IC4") (pin "25") (pinfunction "CLK2MAC_25") (pintype "bidirectional"))
    )
    (net (code "131") (name "unconnected-(IC4-COL-Pad42)") (class "Default")
      (node (ref "IC4") (pin "42") (pinfunction "COL_42") (pintype "bidirectional"))
    )
    (net (code "132") (name "unconnected-(IC4-LED_SPD-Pad27)") (class "Default")
      (node (ref "IC4") (pin "27") (pinfunction "LED_SPD_27") (pintype "bidirectional"))
    )
    (net (code "133") (name "unconnected-(IC4-RXD_2-Pad45)") (class "Default")
      (node (ref "IC4") (pin "45") (pinfunction "RXD_2_45") (pintype "bidirectional"))
    )
    (net (code "134") (name "unconnected-(IC4-RXD_3-Pad46)") (class "Default")
      (node (ref "IC4") (pin "46") (pinfunction "RXD_3_46") (pintype "bidirectional"))
    )
    (net (code "135") (name "unconnected-(IC4-RX_CLK-Pad38)") (class "Default")
      (node (ref "IC4") (pin "38") (pinfunction "RX_CLK_38") (pintype "bidirectional"))
    )
    (net (code "136") (name "unconnected-(IC4-TCK-Pad8)") (class "Default")
      (node (ref "IC4") (pin "8") (pinfunction "TCK_8") (pintype "input"))
    )
    (net (code "137") (name "unconnected-(IC4-TDI-Pad12)") (class "Default")
      (node (ref "IC4") (pin "12") (pinfunction "TDI_12") (pintype "input"))
    )
    (net (code "138") (name "unconnected-(IC4-TDO-Pad9)") (class "Default")
      (node (ref "IC4") (pin "9") (pinfunction "TDO_9") (pintype "output"))
    )
    (net (code "139") (name "unconnected-(IC4-TMS-Pad10)") (class "Default")
      (node (ref "IC4") (pin "10") (pinfunction "TMS_10") (pintype "input"))
    )
    (net (code "140") (name "unconnected-(IC4-TRST_N-Pad11)") (class "Default")
      (node (ref "IC4") (pin "11") (pinfunction "TRST_N_11") (pintype "input"))
    )
    (net (code "141") (name "unconnected-(IC4-TXD_2-Pad5)") (class "Default")
      (node (ref "IC4") (pin "5") (pinfunction "TXD_2_5") (pintype "bidirectional"))
    )
    (net (code "142") (name "unconnected-(IC4-TX_CLK-Pad1)") (class "Default")
      (node (ref "IC4") (pin "1") (pinfunction "TX_CLK_1") (pintype "bidirectional"))
    )
    (net (code "143") (name "unconnected-(IC4-X2-Pad33)") (class "Default")
      (node (ref "IC4") (pin "33") (pinfunction "X2_33") (pintype "output"))
    )
    (net (code "144") (name "unconnected-(JP2-Pad2)") (class "Default")
      (node (ref "JP2") (pin "2") (pinfunction "2_2") (pintype "passive"))
    )
    (net (code "145") (name "unconnected-(JP2-Pad6)") (class "Default")
      (node (ref "JP2") (pin "6") (pinfunction "6_6") (pintype "passive"))
    )
    (net (code "146") (name "unconnected-(JP5-D+-PadD+1)") (class "Default")
      (node (ref "JP5") (pin "D+1") (pinfunction "D+_D+1") (pintype "bidirectional"))
    )
    (net (code "147") (name "unconnected-(JP5-D--PadD-1)") (class "Default")
      (node (ref "JP5") (pin "D-1") (pinfunction "D-_D-1") (pintype "bidirectional"))
    )
    (net (code "148") (name "unconnected-(JP5-ID-PadID1)") (class "Default")
      (node (ref "JP5") (pin "ID1") (pinfunction "ID_ID1") (pintype "bidirectional"))
    )
    (net (code "149") (name "unconnected-(RJ1-PadNC)") (class "Default")
      (node (ref "RJ1") (pin "NC") (pinfunction "NC_NC") (pintype "bidirectional"))
    )
    (net (code "150") (name "unconnected-(SV1-Pad8)") (class "Default")
      (node (ref "SV1") (pin "8") (pinfunction "8_8") (pintype "passive"))
    )
    (net (code "151") (name "unconnected-(U$1-TRI-Pad1)") (class "Default")
      (node (ref "U$1") (pin "1") (pinfunction "TRI_1") (pintype "input"))
    )
    (net (code "152") (name "unconnected-(U$7-TRI-Pad1)") (class "Default")
      (node (ref "U$7") (pin "1") (pinfunction "TRI_1") (pintype "input"))
    )
    (net (code "153") (name "unconnected-(U1-NC-Pad1)") (class "Default")
      (node (ref "U1") (pin "1") (pinfunction "NC_1") (pintype "bidirectional"))
    )
    (net (code "154") (name "unconnected-(U1-RSV-Pad8)") (class "Default")
      (node (ref "U1") (pin "8") (pinfunction "RSV_8") (pintype "bidirectional"))
    )
    (net (code "155") (name "unconnected-(U2A-LINEIN-Pad48)") (class "Default")
      (node (ref "U2") (pin "48") (pinfunction "LINEIN_48") (pintype "bidirectional"))
    )
    (net (code "156") (name "unconnected-(U2A-MICN-Pad2)") (class "Default")
      (node (ref "U2") (pin "2") (pinfunction "MICN_2") (pintype "bidirectional"))
    )
    (net (code "157") (name "unconnected-(U2A-MICP-Pad1)") (class "Default")
      (node (ref "U2") (pin "1") (pinfunction "MICP_1") (pintype "bidirectional"))
    )
    (net (code "158") (name "unconnected-(U2A-TX-Pad27)") (class "Default")
      (node (ref "U2") (pin "27") (pinfunction "TX_27") (pintype "bidirectional"))
    )
    (net (code "159") (name "unconnected-(U2A-VCO-Pad15)") (class "Default")
      (node (ref "U2") (pin "15") (pinfunction "VCO_15") (pintype "bidirectional"))
    )
  )
)
